# OOBD-Tiger.net
KiCad netlist of a schematic drawn in EAGLE
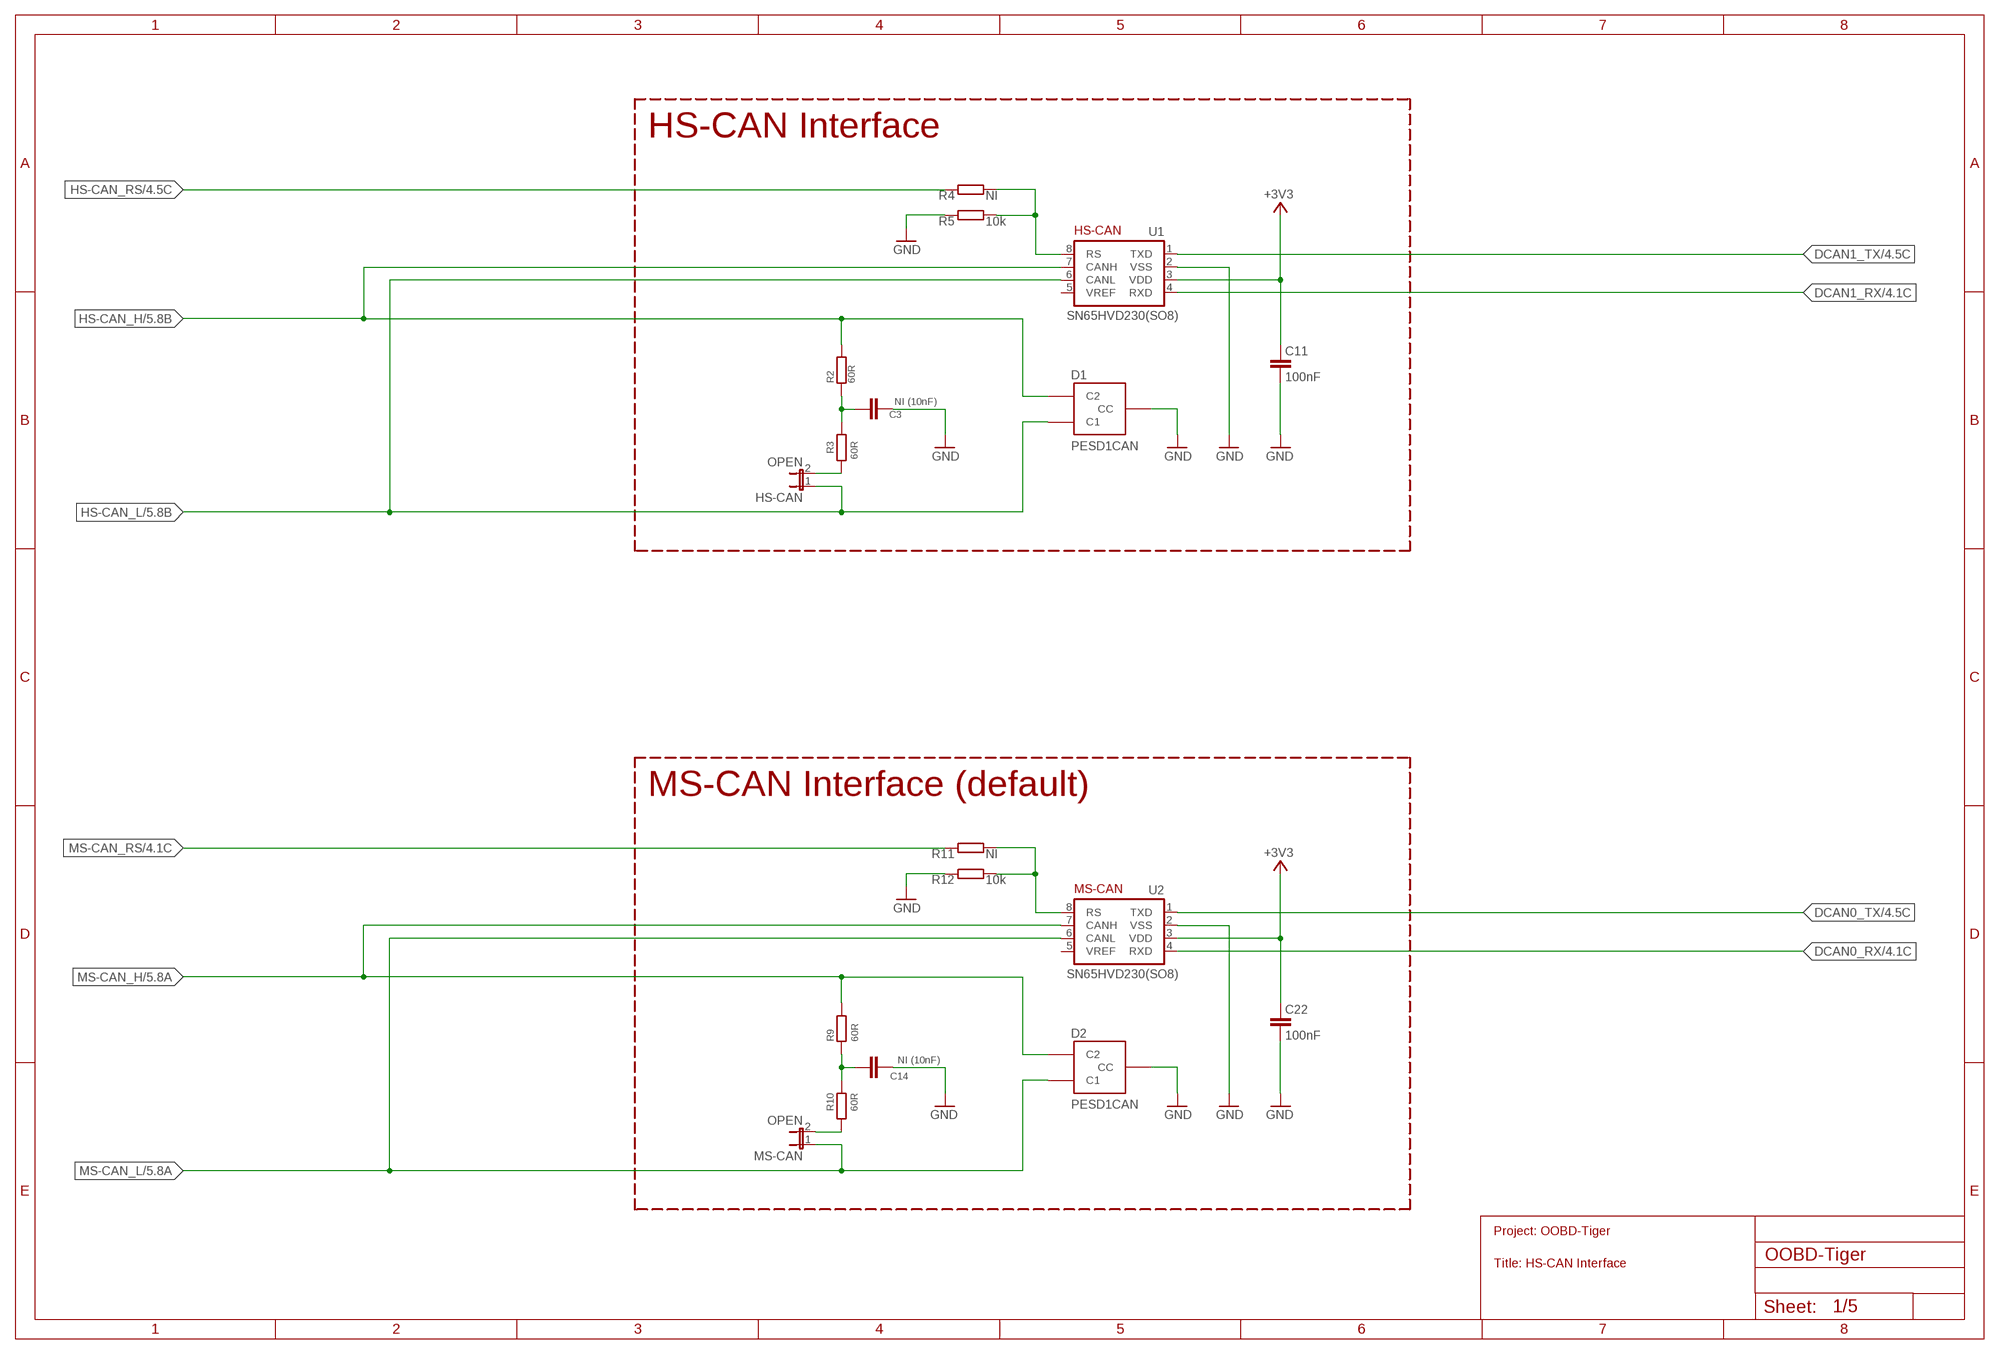
[diagram p0: schematic, sheet 1]
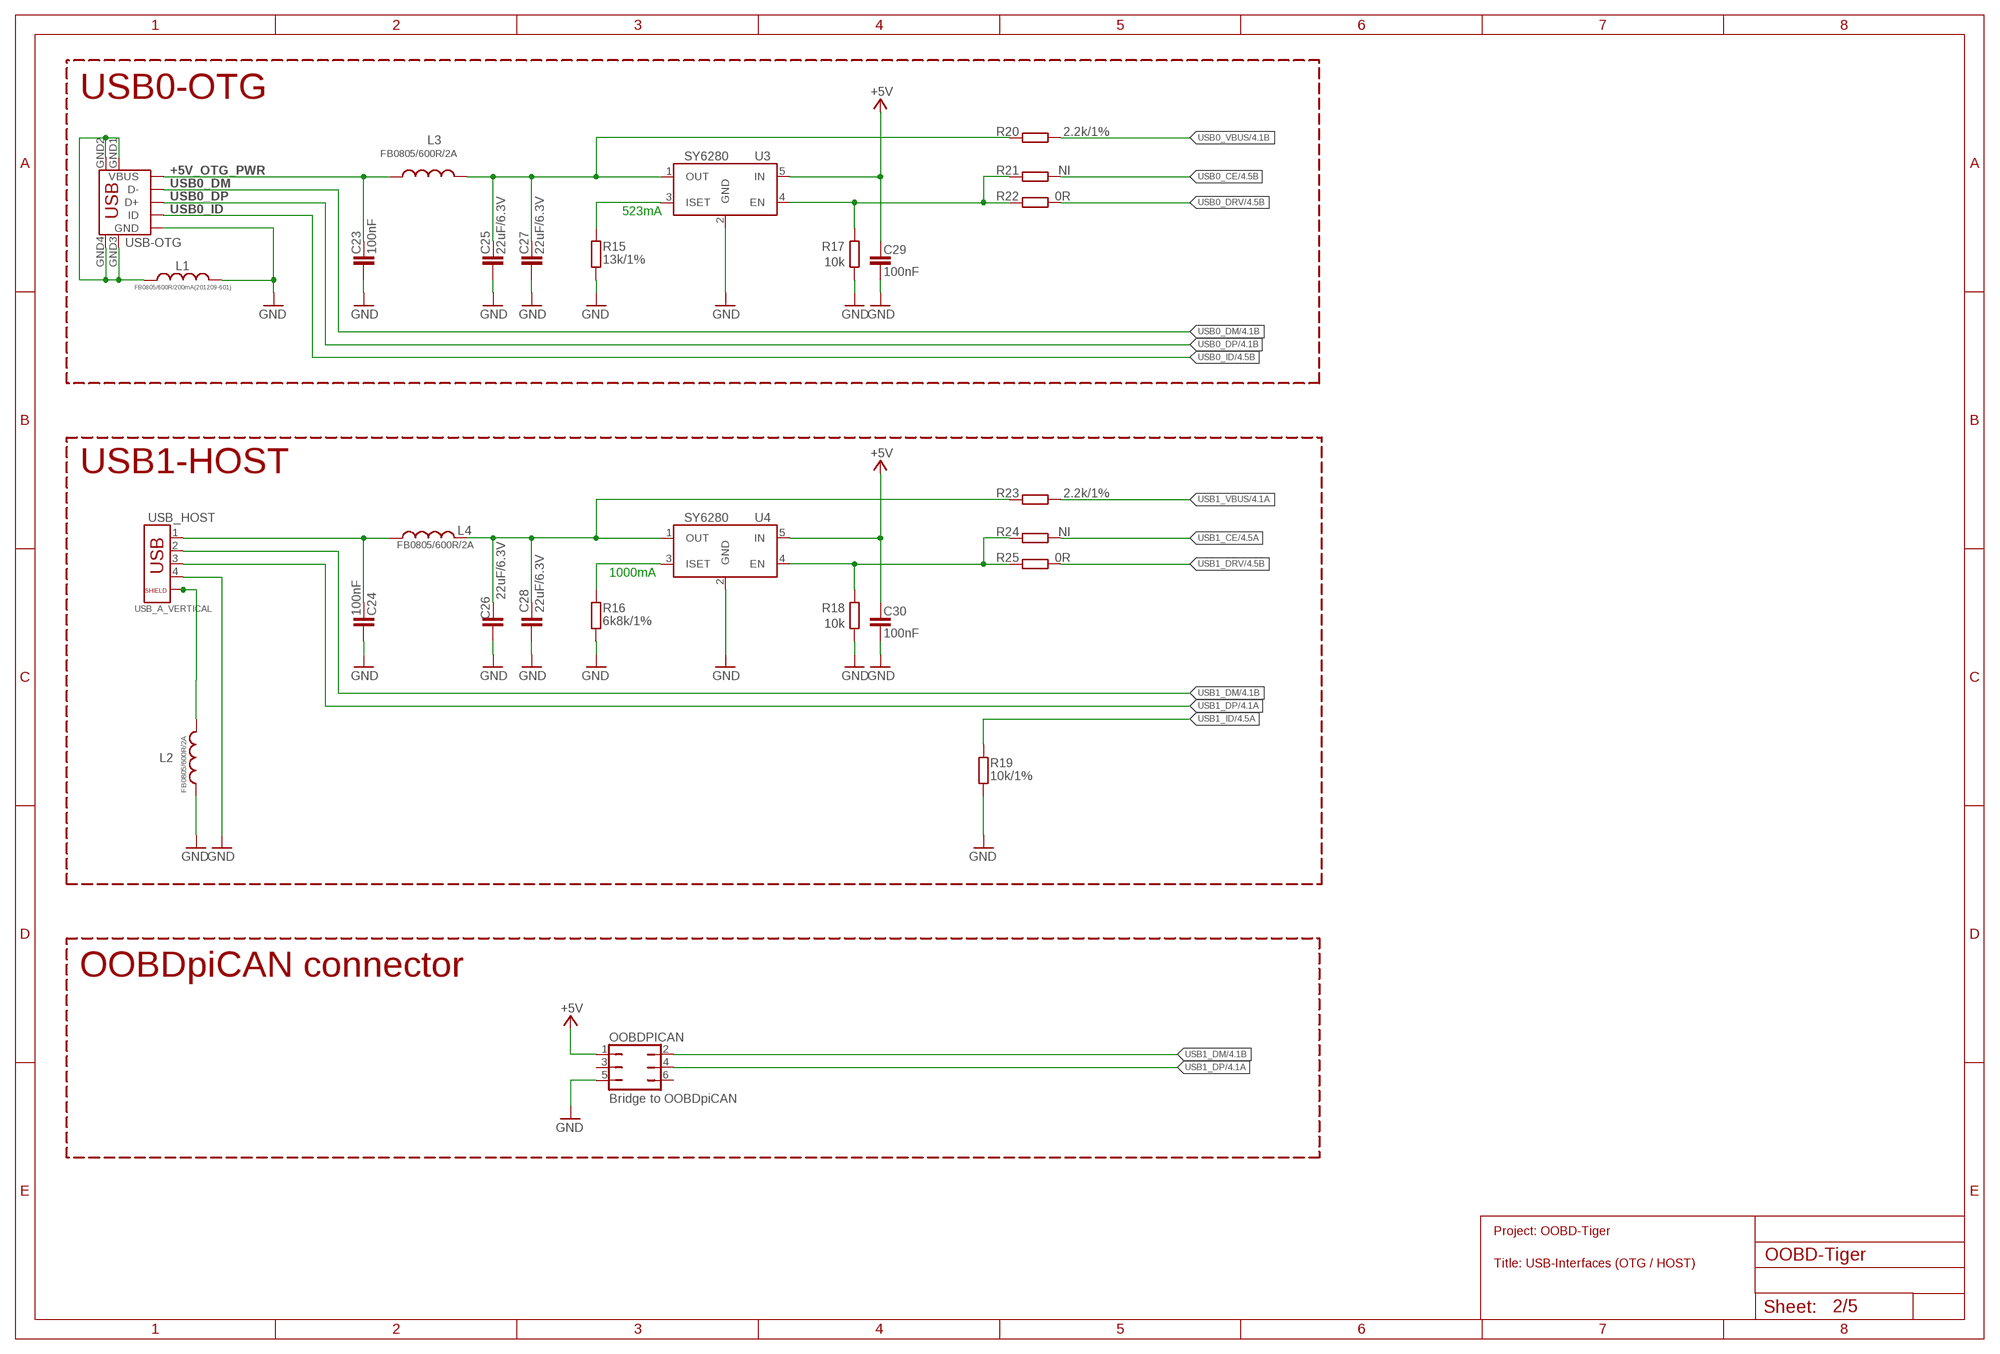
[diagram p1: schematic, sheet 2]
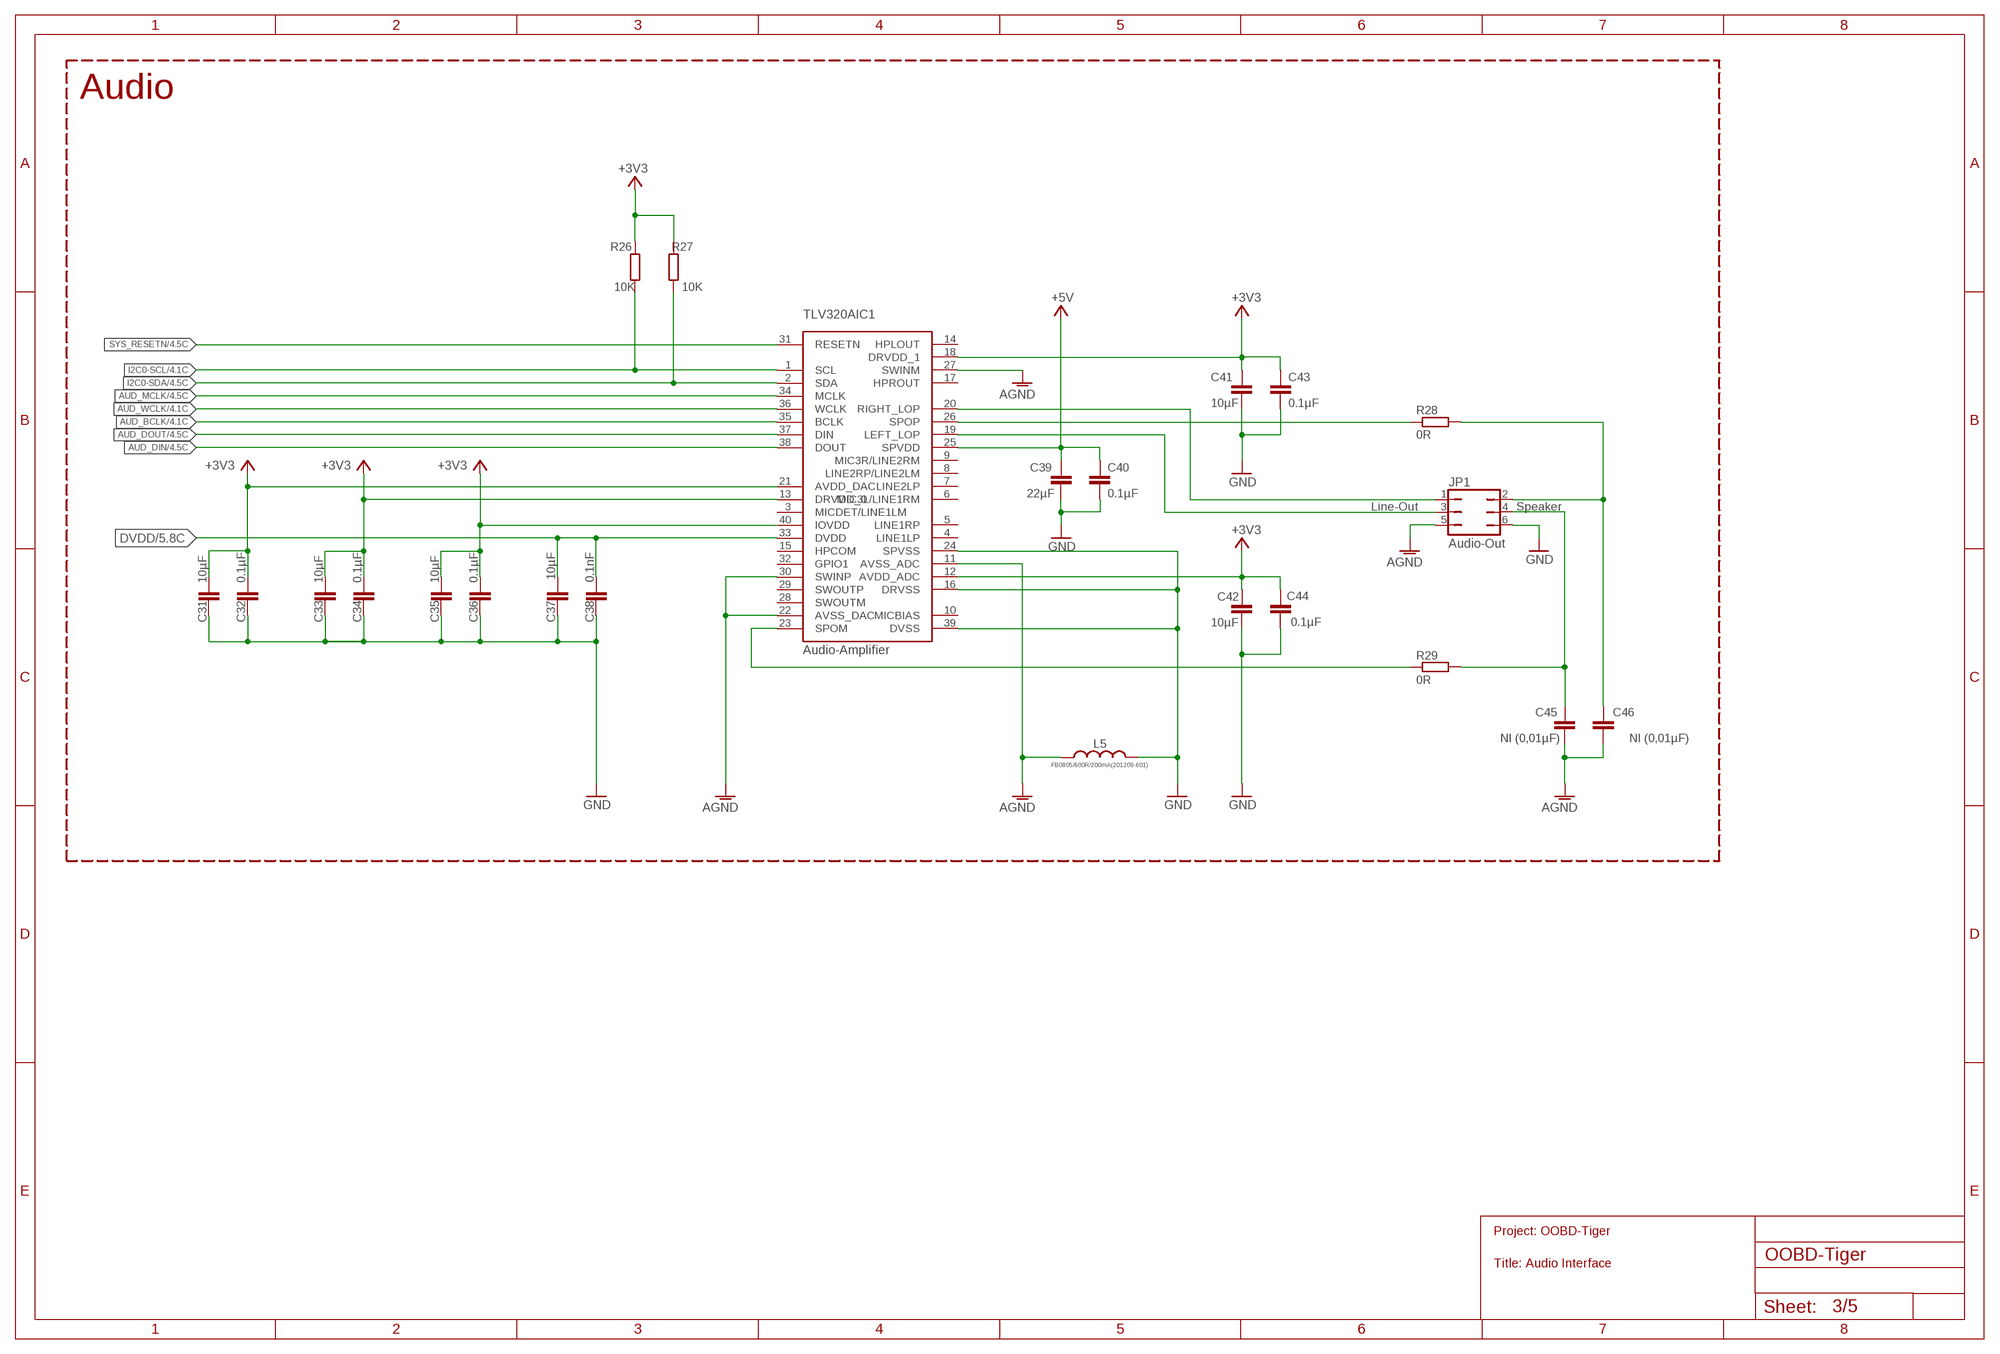
[diagram p2: schematic, sheet 3]
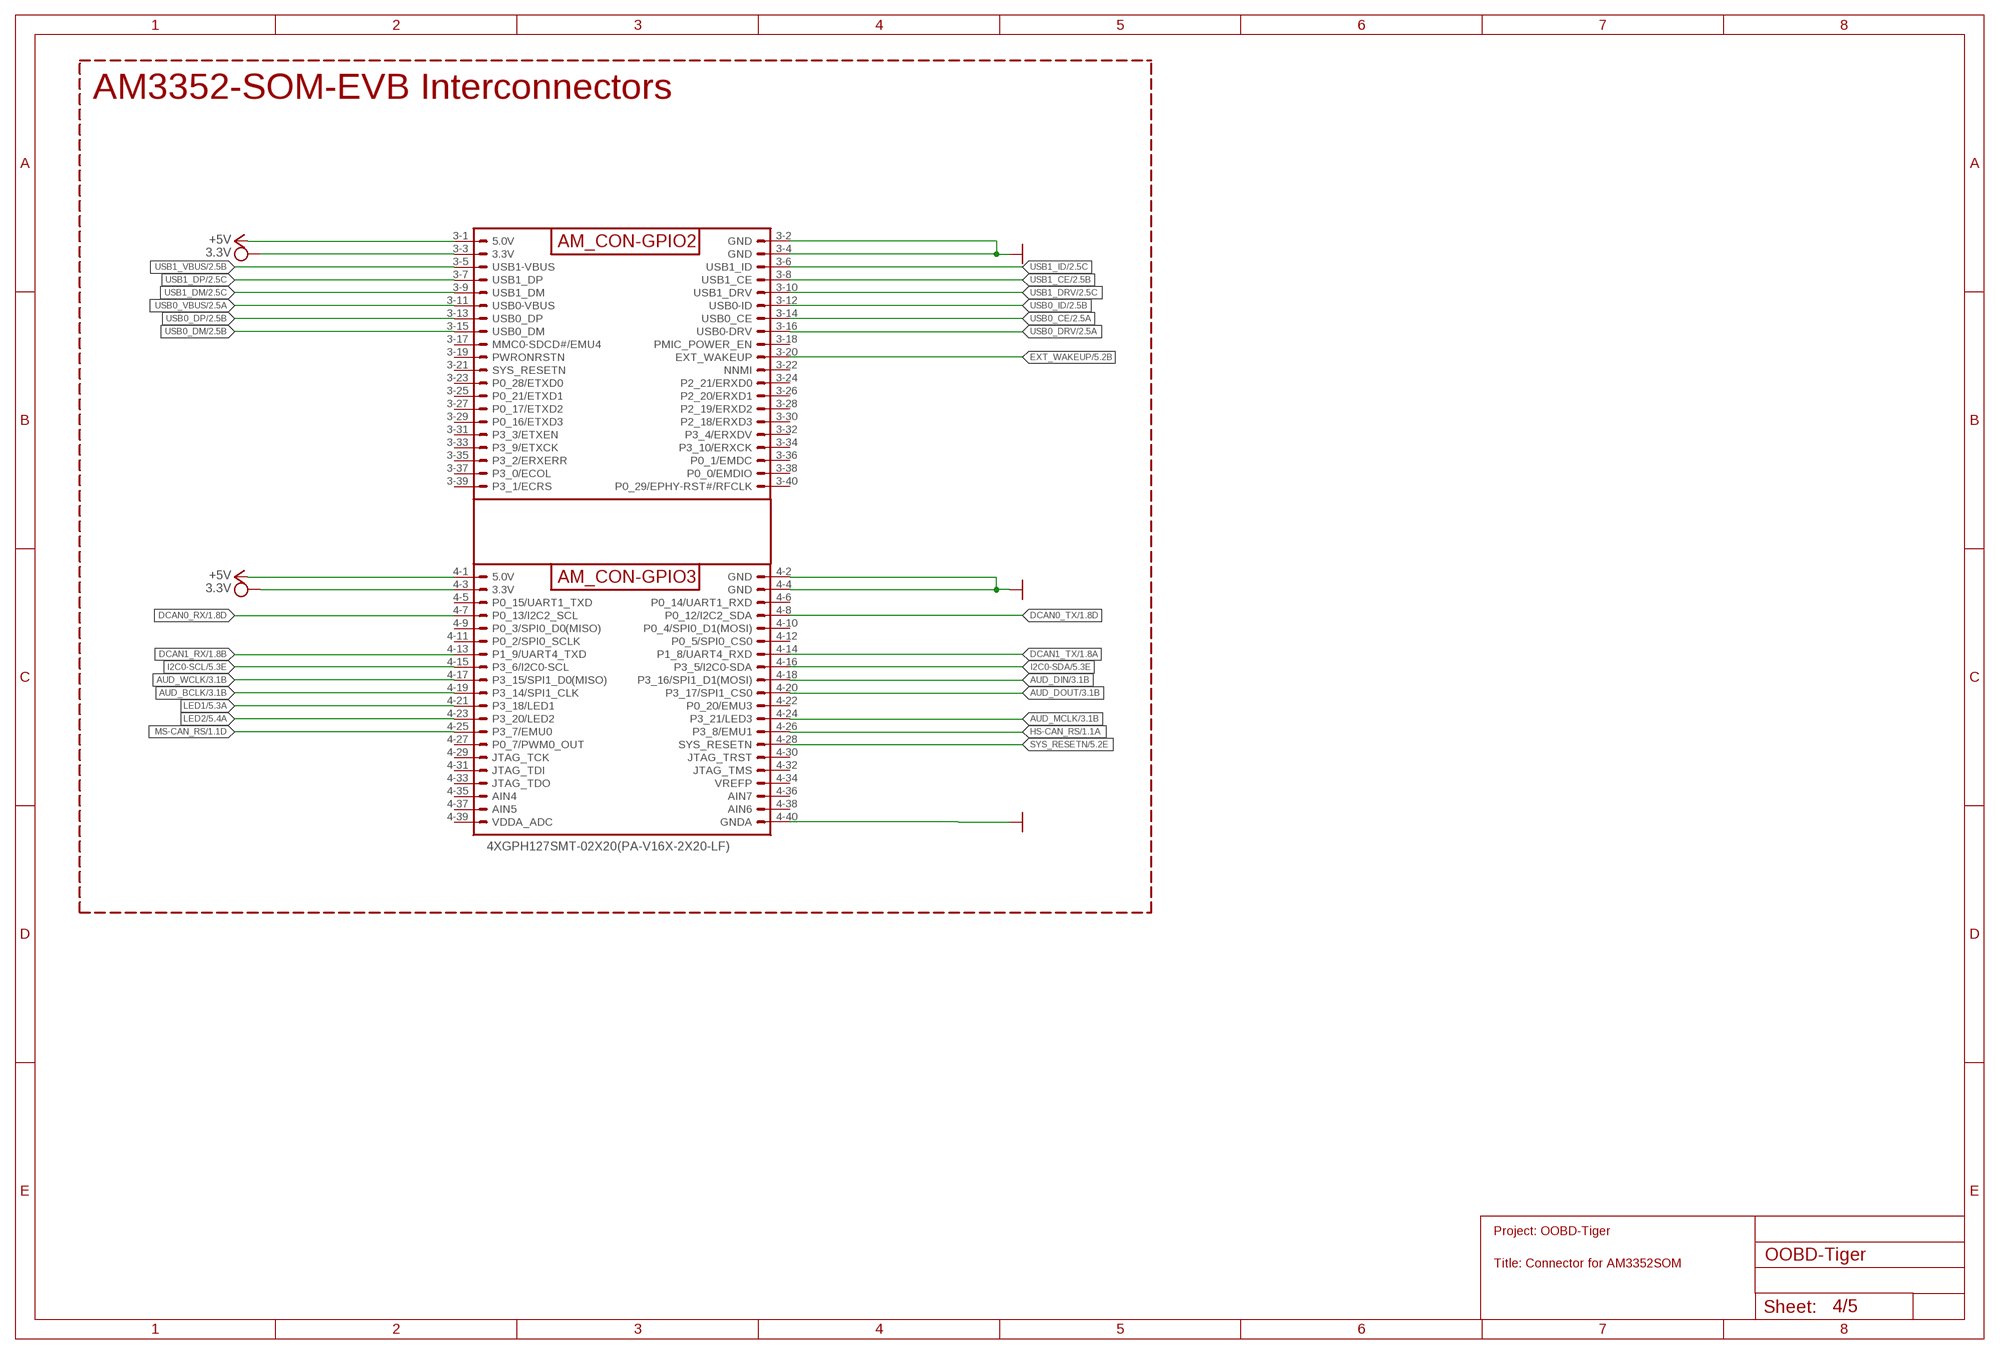
[diagram p3: schematic, sheet 4]
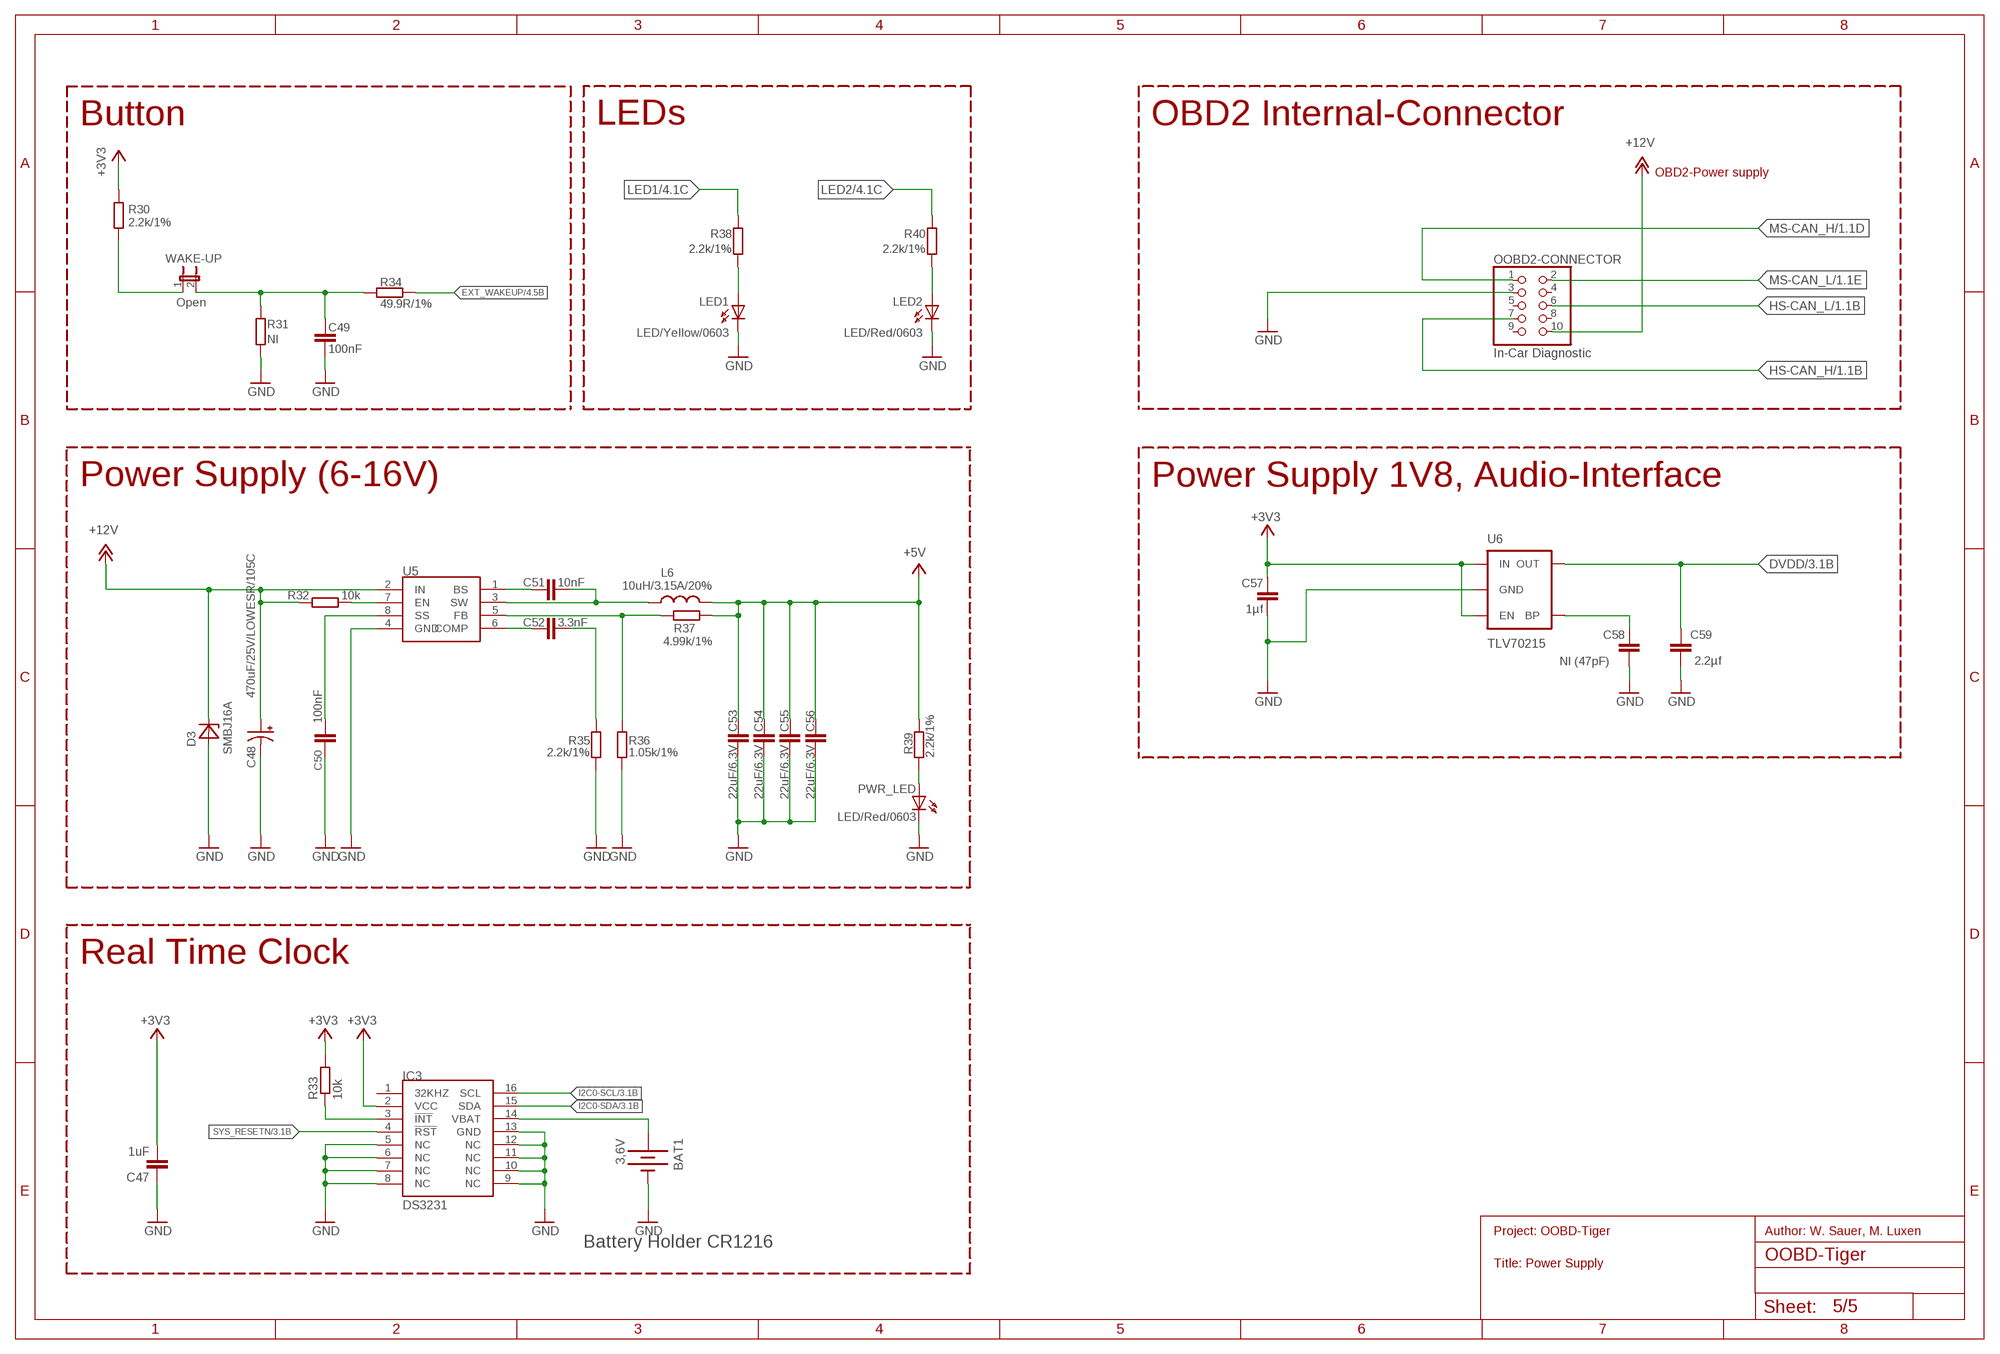
[diagram p4: schematic, sheet 5]

(export (version "E")
  (design (tool "Eeschema 10.0.6"))
  (components
    (comp (ref "C31")
      (value "10µF")
      (footprint "eagle-import:0603-CAP")
      (libsource (lib "eagle-import") (part "CAP0603-CAP"))
    )
    (comp (ref "C32")
      (value "0.1µF")
      (footprint "eagle-import:0603-CAP")
      (libsource (lib "eagle-import") (part "CAP0603-CAP"))
    )
    (comp (ref "C33")
      (value "10µF")
      (footprint "eagle-import:0603-CAP")
      (libsource (lib "eagle-import") (part "CAP0603-CAP"))
    )
    (comp (ref "C34")
      (value "0.1µF")
      (footprint "eagle-import:0603-CAP")
      (libsource (lib "eagle-import") (part "CAP0603-CAP"))
    )
    (comp (ref "C35")
      (value "10µF")
      (footprint "eagle-import:0603-CAP")
      (libsource (lib "eagle-import") (part "CAP0603-CAP"))
    )
    (comp (ref "C36")
      (value "0.1µF")
      (footprint "eagle-import:0603-CAP")
      (libsource (lib "eagle-import") (part "CAP0603-CAP"))
    )
    (comp (ref "C37")
      (value "10µF")
      (footprint "eagle-import:0603-CAP")
      (libsource (lib "eagle-import") (part "CAP0603-CAP"))
    )
    (comp (ref "C38")
      (value "0.1nF")
      (footprint "eagle-import:0603-CAP")
      (libsource (lib "eagle-import") (part "CAP0603-CAP"))
    )
    (comp (ref "C39")
      (value "22µF")
      (footprint "eagle-import:0603-CAP")
      (libsource (lib "eagle-import") (part "CAP0603-CAP"))
    )
    (comp (ref "C40")
      (value "0.1µF")
      (footprint "eagle-import:0603-CAP")
      (libsource (lib "eagle-import") (part "CAP0603-CAP"))
    )
    (comp (ref "C41")
      (value "10µF")
      (footprint "eagle-import:0603-CAP")
      (libsource (lib "eagle-import") (part "CAP0603-CAP"))
    )
    (comp (ref "C42")
      (value "10µF")
      (footprint "eagle-import:0603-CAP")
      (libsource (lib "eagle-import") (part "CAP0603-CAP"))
    )
    (comp (ref "C43")
      (value "0.1µF")
      (footprint "eagle-import:0603-CAP")
      (libsource (lib "eagle-import") (part "CAP0603-CAP"))
    )
    (comp (ref "C44")
      (value "0.1µF")
      (footprint "eagle-import:0603-CAP")
      (libsource (lib "eagle-import") (part "CAP0603-CAP"))
    )
    (comp (ref "C45")
      (value "NI (0,01µF)")
      (footprint "eagle-import:0603-CAP")
      (libsource (lib "eagle-import") (part "CAP0603-CAP"))
    )
    (comp (ref "C46")
      (value "NI (0,01µF)")
      (footprint "eagle-import:0603-CAP")
      (libsource (lib "eagle-import") (part "CAP0603-CAP"))
    )
    (comp (ref "JP1")
      (value "Audio-Out")
      (footprint "eagle-import:JP3Q")
      (libsource (lib "eagle-import") (part "JP3Q"))
    )
    (comp (ref "L5")
      (value "FB0805/600R/200mA(201209-601)")
      (footprint "eagle-import:L0603")
      (libsource (lib "eagle-import") (part "L-USL0603"))
    )
    (comp (ref "R26")
      (value "10K")
      (footprint "eagle-import:R0603")
      (libsource (lib "eagle-import") (part "resistor_R-EU_R0603"))
    )
    (comp (ref "R27")
      (value "10K")
      (footprint "eagle-import:R0603")
      (libsource (lib "eagle-import") (part "resistor_R-EU_R0603"))
    )
    (comp (ref "R28")
      (value "0R")
      (footprint "eagle-import:R0805")
      (libsource (lib "eagle-import") (part "resistor_R-EU_R0805"))
    )
    (comp (ref "R29")
      (value "0R")
      (footprint "eagle-import:R0805")
      (libsource (lib "eagle-import") (part "resistor_R-EU_R0805"))
    )
    (comp (ref "TLV320AIC1")
      (value "Audio-Amplifier")
      (footprint "eagle-import:QFN40-6X6")
      (libsource (lib "eagle-import") (part "TLV320AIC3107"))
    )
    (comp (ref "C3")
      (value "NI (10nF)")
      (footprint "eagle-import:C0603")
      (libsource (lib "eagle-import") (part "resistor_C-EUC0603"))
    )
    (comp (ref "C11")
      (value "100nF")
      (footprint "eagle-import:C0603K")
      (libsource (lib "eagle-import") (part "C-EUC0603K"))
    )
    (comp (ref "C14")
      (value "NI (10nF)")
      (footprint "eagle-import:C0603")
      (libsource (lib "eagle-import") (part "resistor_C-EUC0603"))
    )
    (comp (ref "C22")
      (value "100nF")
      (footprint "eagle-import:C0603K")
      (libsource (lib "eagle-import") (part "C-EUC0603K"))
    )
    (comp (ref "D1")
      (value "PESD1CAN")
      (footprint "eagle-import:SOT23")
      (libsource (lib "eagle-import") (part "PESD1CAN"))
    )
    (comp (ref "D2")
      (value "PESD1CAN")
      (footprint "eagle-import:SOT23")
      (libsource (lib "eagle-import") (part "PESD1CAN"))
    )
    (comp (ref "HS-CAN")
      (value "OPEN")
      (footprint "eagle-import:1X02")
      (libsource (lib "eagle-import") (part "JUMPER-2PTH"))
    )
    (comp (ref "MS-CAN")
      (value "OPEN")
      (footprint "eagle-import:1X02")
      (libsource (lib "eagle-import") (part "JUMPER-2PTH"))
    )
    (comp (ref "R2")
      (value "60R")
      (footprint "eagle-import:R0603")
      (libsource (lib "eagle-import") (part "resistor_R-EU_R0603"))
    )
    (comp (ref "R3")
      (value "60R")
      (footprint "eagle-import:R0603")
      (libsource (lib "eagle-import") (part "resistor_R-EU_R0603"))
    )
    (comp (ref "R4")
      (value "NI")
      (footprint "eagle-import:R0603")
      (libsource (lib "eagle-import") (part "R-EU_R0603"))
    )
    (comp (ref "R5")
      (value "10k")
      (footprint "eagle-import:R0603")
      (libsource (lib "eagle-import") (part "R-EU_R0603"))
    )
    (comp (ref "R9")
      (value "60R")
      (footprint "eagle-import:R0603")
      (libsource (lib "eagle-import") (part "resistor_R-EU_R0603"))
    )
    (comp (ref "R10")
      (value "60R")
      (footprint "eagle-import:R0603")
      (libsource (lib "eagle-import") (part "resistor_R-EU_R0603"))
    )
    (comp (ref "R11")
      (value "NI")
      (footprint "eagle-import:R0603")
      (libsource (lib "eagle-import") (part "R-EU_R0603"))
    )
    (comp (ref "R12")
      (value "10k")
      (footprint "eagle-import:R0603")
      (libsource (lib "eagle-import") (part "R-EU_R0603"))
    )
    (comp (ref "U1")
      (value "SN65HVD230(SO8)")
      (footprint "eagle-import:SO-08")
      (libsource (lib "eagle-import") (part "MCP2551"))
    )
    (comp (ref "U2")
      (value "SN65HVD230(SO8)")
      (footprint "eagle-import:SO-08")
      (libsource (lib "eagle-import") (part "MCP2551"))
    )
    (comp (ref "BAT1")
      (value "3,6V")
      (footprint "eagle-import:BATTCON_12MM_PTH")
      (libsource (lib "eagle-import") (part "BATTERY12PTH"))
    )
    (comp (ref "C47")
      (value "1uF")
      (footprint "eagle-import:C0603")
      (libsource (lib "eagle-import") (part "C-EUC0603"))
    )
    (comp (ref "C48")
      (value "470uF/25V/LOWESR/105C")
      (footprint "eagle-import:PANASONIC_D")
      (libsource (lib "eagle-import") (part "47UF-50V-20%(ELECT)"))
    )
    (comp (ref "C49")
      (value "100nF")
      (footprint "eagle-import:C0603")
      (libsource (lib "eagle-import") (part "C-EUC0603"))
    )
    (comp (ref "C50")
      (value "100nF")
      (footprint "eagle-import:C0603")
      (libsource (lib "eagle-import") (part "C-EUC0603"))
    )
    (comp (ref "C51")
      (value "10nF")
      (footprint "eagle-import:C0603")
      (libsource (lib "eagle-import") (part "C-EUC0603"))
    )
    (comp (ref "C52")
      (value "3.3nF")
      (footprint "eagle-import:C0603")
      (libsource (lib "eagle-import") (part "C-EUC0603"))
    )
    (comp (ref "C53")
      (value "22uF/6.3V")
      (footprint "eagle-import:C0603")
      (libsource (lib "eagle-import") (part "C-EUC0603"))
    )
    (comp (ref "C54")
      (value "22uF/6.3V")
      (footprint "eagle-import:C0603")
      (libsource (lib "eagle-import") (part "C-EUC0603"))
    )
    (comp (ref "C55")
      (value "22uF/6.3V")
      (footprint "eagle-import:C0603")
      (libsource (lib "eagle-import") (part "C-EUC0603"))
    )
    (comp (ref "C56")
      (value "22uF/6.3V")
      (footprint "eagle-import:C0603")
      (libsource (lib "eagle-import") (part "C-EUC0603"))
    )
    (comp (ref "C57")
      (value "1µf")
      (footprint "eagle-import:0603-CAP")
      (libsource (lib "eagle-import") (part "CAP0603-CAP"))
    )
    (comp (ref "C58")
      (value "NI (47pF)")
      (footprint "eagle-import:0603-CAP")
      (libsource (lib "eagle-import") (part "CAP0603-CAP"))
    )
    (comp (ref "C59")
      (value "2.2µf")
      (footprint "eagle-import:0603-CAP")
      (libsource (lib "eagle-import") (part "CAP0603-CAP"))
    )
    (comp (ref "D3")
      (value "SMBJ16A")
      (footprint "eagle-import:DO214AA")
      (libsource (lib "eagle-import") (part "SMBJ16A"))
    )
    (comp (ref "IC3")
      (value "DS3231")
      (footprint "eagle-import:SOIC-16W")
      (libsource (lib "eagle-import") (part "DS3231SOIC-16W"))
    )
    (comp (ref "L6")
      (value "10uH/3.15A/20%")
      (footprint "eagle-import:8X8MM_3131")
      (libsource (lib "eagle-import") (part "LLQH88PN100M38"))
    )
    (comp (ref "LED1")
      (value "LED/Yellow/0603")
      (footprint "eagle-import:LED_0603")
      (libsource (lib "eagle-import") (part "LEDLED_0603"))
    )
    (comp (ref "LED2")
      (value "LED/Red/0603")
      (footprint "eagle-import:LED_0603")
      (libsource (lib "eagle-import") (part "LEDLED_0603"))
    )
    (comp (ref "OOBD2-CONNECTOR")
      (value "In-Car Diagnostic")
      (footprint "eagle-import:2X05_90")
      (libsource (lib "eagle-import") (part "PINHD-2X5/90"))
    )
    (comp (ref "PWR_LED")
      (value "LED/Red/0603")
      (footprint "eagle-import:LED-0603")
      (libsource (lib "eagle-import") (part "LED0603DWS"))
    )
    (comp (ref "R30")
      (value "2.2k/1%")
      (footprint "eagle-import:R0603")
      (libsource (lib "eagle-import") (part "R-EU_R0603"))
    )
    (comp (ref "R31")
      (value "NI")
      (footprint "eagle-import:R0603")
      (libsource (lib "eagle-import") (part "R-EU_R0603"))
    )
    (comp (ref "R32")
      (value "10k")
      (footprint "eagle-import:R0603")
      (libsource (lib "eagle-import") (part "R-EU_R0603"))
    )
    (comp (ref "R33")
      (value "10k")
      (footprint "eagle-import:R0603")
      (libsource (lib "eagle-import") (part "R-EU_R0603"))
    )
    (comp (ref "R34")
      (value "49.9R/1%")
      (footprint "eagle-import:R0603")
      (libsource (lib "eagle-import") (part "R-EU_R0603"))
    )
    (comp (ref "R35")
      (value "2.2k/1%")
      (footprint "eagle-import:R0603")
      (libsource (lib "eagle-import") (part "R-EU_R0603"))
    )
    (comp (ref "R36")
      (value "1.05k/1%")
      (footprint "eagle-import:R0603")
      (libsource (lib "eagle-import") (part "R-EU_R0603"))
    )
    (comp (ref "R37")
      (value "4.99k/1%")
      (footprint "eagle-import:R0603")
      (libsource (lib "eagle-import") (part "R-EU_R0603"))
    )
    (comp (ref "R38")
      (value "2.2k/1%")
      (footprint "eagle-import:R0603")
      (libsource (lib "eagle-import") (part "R-EU_R0603"))
    )
    (comp (ref "R39")
      (value "2.2k/1%")
      (footprint "eagle-import:R0603")
      (libsource (lib "eagle-import") (part "R-EU_R0603"))
    )
    (comp (ref "R40")
      (value "2.2k/1%")
      (footprint "eagle-import:R0603")
      (libsource (lib "eagle-import") (part "R-EU_R0603"))
    )
    (comp (ref "U5")
      (value "MP1482")
      (footprint "eagle-import:SOIC8")
      (libsource (lib "eagle-import") (part "MP1482"))
    )
    (comp (ref "U6")
      (value "TLV70215")
      (footprint "eagle-import:SOT23-5")
      (libsource (lib "eagle-import") (part "V_REG_LDOSMD"))
    )
    (comp (ref "WAKE-UP")
      (value "Open")
      (footprint "eagle-import:1X02_LOCK")
      (libsource (lib "eagle-import") (part "JUMPER-2PTH_LOCK"))
    )
    (comp (ref "C23")
      (value "100nF")
      (footprint "eagle-import:C0603K")
      (libsource (lib "eagle-import") (part "C-EUC0603K"))
    )
    (comp (ref "C24")
      (value "100nF")
      (footprint "eagle-import:C0603K")
      (libsource (lib "eagle-import") (part "C-EUC0603K"))
    )
    (comp (ref "C25")
      (value "22uF/6.3V")
      (footprint "eagle-import:C0603")
      (libsource (lib "eagle-import") (part "C-EUC0603"))
    )
    (comp (ref "C26")
      (value "22uF/6.3V")
      (footprint "eagle-import:C0603")
      (libsource (lib "eagle-import") (part "C-EUC0603"))
    )
    (comp (ref "C27")
      (value "22uF/6.3V")
      (footprint "eagle-import:C0603")
      (libsource (lib "eagle-import") (part "C-EUC0603"))
    )
    (comp (ref "C28")
      (value "22uF/6.3V")
      (footprint "eagle-import:C0603")
      (libsource (lib "eagle-import") (part "C-EUC0603"))
    )
    (comp (ref "C29")
      (value "100nF")
      (footprint "eagle-import:C0603K")
      (libsource (lib "eagle-import") (part "C-EUC0603K"))
    )
    (comp (ref "C30")
      (value "100nF")
      (footprint "eagle-import:C0603K")
      (libsource (lib "eagle-import") (part "C-EUC0603K"))
    )
    (comp (ref "L1")
      (value "FB0805/600R/200mA(201209-601)")
      (footprint "eagle-import:L0603")
      (libsource (lib "eagle-import") (part "L-USL0603"))
    )
    (comp (ref "L2")
      (value "FB0805/600R/2A")
      (footprint "eagle-import:L0603")
      (libsource (lib "eagle-import") (part "L-USL0603"))
    )
    (comp (ref "L3")
      (value "FB0805/600R/2A")
      (footprint "eagle-import:L0603")
      (libsource (lib "eagle-import") (part "L-USL0603"))
    )
    (comp (ref "L4")
      (value "FB0805/600R/2A")
      (footprint "eagle-import:L0603")
      (libsource (lib "eagle-import") (part "L-USL0603"))
    )
    (comp (ref "OOBDPICAN")
      (value "Bridge to OOBDpiCAN")
      (footprint "eagle-import:JP3Q")
      (libsource (lib "eagle-import") (part "JP3Q"))
    )
    (comp (ref "R15")
      (value "13k/1%")
      (footprint "eagle-import:R0603")
      (libsource (lib "eagle-import") (part "R-EU_R0603"))
    )
    (comp (ref "R16")
      (value "6k8k/1%")
      (footprint "eagle-import:R0603")
      (libsource (lib "eagle-import") (part "R-EU_R0603"))
    )
    (comp (ref "R17")
      (value "10k")
      (footprint "eagle-import:R0603")
      (libsource (lib "eagle-import") (part "R-EU_R0603"))
    )
    (comp (ref "R18")
      (value "10k")
      (footprint "eagle-import:R0603")
      (libsource (lib "eagle-import") (part "R-EU_R0603"))
    )
    (comp (ref "R19")
      (value "10k/1%")
      (footprint "eagle-import:R0603")
      (libsource (lib "eagle-import") (part "R-EU_R0603"))
    )
    (comp (ref "R20")
      (value "2.2k/1%")
      (footprint "eagle-import:R0603")
      (libsource (lib "eagle-import") (part "R-EU_R0603"))
    )
    (comp (ref "R21")
      (value "NI")
      (footprint "eagle-import:R0603")
      (libsource (lib "eagle-import") (part "R-EU_R0603"))
    )
    (comp (ref "R22")
      (value "0R")
      (footprint "eagle-import:R0603")
      (libsource (lib "eagle-import") (part "R-EU_R0603"))
    )
    (comp (ref "R23")
      (value "2.2k/1%")
      (footprint "eagle-import:R0603")
      (libsource (lib "eagle-import") (part "R-EU_R0603"))
    )
    (comp (ref "R24")
      (value "NI")
      (footprint "eagle-import:R0603")
      (libsource (lib "eagle-import") (part "R-EU_R0603"))
    )
    (comp (ref "R25")
      (value "0R")
      (footprint "eagle-import:R0603")
      (libsource (lib "eagle-import") (part "R-EU_R0603"))
    )
    (comp (ref "U3")
      (value "SY6280")
      (footprint "eagle-import:SOT23-5")
      (libsource (lib "eagle-import") (part "SY6280"))
    )
    (comp (ref "U4")
      (value "SY6280")
      (footprint "eagle-import:SOT23-5")
      (libsource (lib "eagle-import") (part "SY6280"))
    )
    (comp (ref "USB_HOST")
      (value "USB_A_VERTICAL")
      (footprint "eagle-import:USB_PN87520_DEV_PTH")
      (libsource (lib "eagle-import") (part "USB_SHIELD1"))
    )
    (comp (ref "USB_OTG")
      (value "USB-OTG")
      (footprint "eagle-import:USB_MINI_9PIN")
      (libsource (lib "eagle-import") (part "MINI_USB9"))
    )
    (comp (ref "AM3352-SOM-EVB-PLATFORM")
      (value "4XGPH127SMT-02X20(PA-V16X-2X20-LF)")
      (footprint "eagle-import:OOBD-TIGER-AM3352-SOM")
      (libsource (lib "eagle-import") (part "OOBD-TIGER-AM3352-SOM---4XGPH127SMT-02X20(PA-V16X-2X20-LF)"))
    )
  )
  (nets
    (net (code "1") (name "+3V3") (class "Default")
      (node (ref "C11") (pin "1") (pinfunction "1_1") (pintype "passive"))
      (node (ref "C22") (pin "1") (pinfunction "1_1") (pintype "passive"))
      (node (ref "C31") (pin "2") (pinfunction "2_2") (pintype "passive"))
      (node (ref "C32") (pin "2") (pinfunction "2_2") (pintype "passive"))
      (node (ref "C33") (pin "2") (pinfunction "2_2") (pintype "passive"))
      (node (ref "C34") (pin "2") (pinfunction "2_2") (pintype "passive"))
      (node (ref "C35") (pin "2") (pinfunction "2_2") (pintype "passive"))
      (node (ref "C36") (pin "2") (pinfunction "2_2") (pintype "passive"))
      (node (ref "C41") (pin "1") (pinfunction "1_1") (pintype "passive"))
      (node (ref "C42") (pin "1") (pinfunction "1_1") (pintype "passive"))
      (node (ref "C43") (pin "1") (pinfunction "1_1") (pintype "passive"))
      (node (ref "C44") (pin "1") (pinfunction "1_1") (pintype "passive"))
      (node (ref "C47") (pin "2") (pinfunction "2_2") (pintype "passive"))
      (node (ref "C57") (pin "2") (pinfunction "2_2") (pintype "passive"))
      (node (ref "IC3") (pin "2") (pinfunction "VCC_2") (pintype "bidirectional"))
      (node (ref "R26") (pin "2") (pinfunction "2_2") (pintype "passive"))
      (node (ref "R27") (pin "2") (pinfunction "2_2") (pintype "passive"))
      (node (ref "R30") (pin "2") (pinfunction "2_2") (pintype "passive"))
      (node (ref "R33") (pin "2") (pinfunction "2_2") (pintype "passive"))
      (node (ref "TLV320AIC1") (pin "12") (pinfunction "AVDD_ADC_12") (pintype "bidirectional"))
      (node (ref "TLV320AIC1") (pin "13") (pinfunction "DRVDD_0_13") (pintype "bidirectional"))
      (node (ref "TLV320AIC1") (pin "18") (pinfunction "DRVDD_1_18") (pintype "bidirectional"))
      (node (ref "TLV320AIC1") (pin "21") (pinfunction "AVDD_DAC_21") (pintype "bidirectional"))
      (node (ref "TLV320AIC1") (pin "40") (pinfunction "IOVDD_40") (pintype "bidirectional"))
      (node (ref "U1") (pin "3") (pinfunction "VDD_3") (pintype "power_in"))
      (node (ref "U2") (pin "3") (pinfunction "VDD_3") (pintype "power_in"))
      (node (ref "U6") (pin "1") (pinfunction "IN_1") (pintype "input"))
      (node (ref "U6") (pin "3") (pinfunction "EN_3") (pintype "input"))
    )
    (net (code "2") (name "+5V") (class "Default")
      (node (ref "AM3352-SOM-EVB-PLATFORM") (pin "3-1") (pinfunction "5.0V_3-1") (pintype "passive"))
      (node (ref "AM3352-SOM-EVB-PLATFORM") (pin "4-1") (pinfunction "5.0V_4-1") (pintype "passive"))
      (node (ref "C29") (pin "1") (pinfunction "1_1") (pintype "passive"))
      (node (ref "C30") (pin "1") (pinfunction "1_1") (pintype "passive"))
      (node (ref "C39") (pin "2") (pinfunction "2_2") (pintype "passive"))
      (node (ref "C40") (pin "2") (pinfunction "2_2") (pintype "passive"))
      (node (ref "C53") (pin "1") (pinfunction "1_1") (pintype "passive"))
      (node (ref "C54") (pin "1") (pinfunction "1_1") (pintype "passive"))
      (node (ref "C55") (pin "1") (pinfunction "1_1") (pintype "passive"))
      (node (ref "C56") (pin "1") (pinfunction "1_1") (pintype "passive"))
      (node (ref "L6") (pin "2") (pinfunction "2_2") (pintype "passive"))
      (node (ref "OOBDPICAN") (pin "1") (pinfunction "1_1") (pintype "passive"))
      (node (ref "R37") (pin "2") (pinfunction "2_2") (pintype "passive"))
      (node (ref "R39") (pin "1") (pinfunction "1_1") (pintype "passive"))
      (node (ref "TLV320AIC1") (pin "25") (pinfunction "SPVDD_25") (pintype "bidirectional"))
      (node (ref "U3") (pin "5") (pinfunction "IN_5") (pintype "power_in"))
      (node (ref "U4") (pin "5") (pinfunction "IN_5") (pintype "power_in"))
    )
    (net (code "3") (name "+5V_OTG_PWR") (class "Default")
      (node (ref "C23") (pin "1") (pinfunction "1_1") (pintype "passive"))
      (node (ref "L3") (pin "1") (pinfunction "1_1") (pintype "passive"))
      (node (ref "USB_OTG") (pin "VBUS") (pinfunction "VBUS_VBUS") (pintype "power_in"))
    )
    (net (code "4") (name "+12V") (class "Default")
      (node (ref "C48") (pin "+") (pinfunction "+_+") (pintype "passive"))
      (node (ref "D3") (pin "C") (pinfunction "C_C") (pintype "passive"))
      (node (ref "OOBD2-CONNECTOR") (pin "10") (pinfunction "10_10") (pintype "passive"))
      (node (ref "R32") (pin "1") (pinfunction "1_1") (pintype "passive"))
      (node (ref "U5") (pin "2") (pinfunction "IN_2") (pintype "bidirectional"))
    )
    (net (code "5") (name "3V3") (class "Default")
      (node (ref "AM3352-SOM-EVB-PLATFORM") (pin "3-3") (pinfunction "3.3V_3-3") (pintype "passive"))
      (node (ref "AM3352-SOM-EVB-PLATFORM") (pin "4-3") (pinfunction "3.3V_4-3") (pintype "passive"))
    )
    (net (code "6") (name "AGND") (class "Default")
      (node (ref "C45") (pin "1") (pinfunction "1_1") (pintype "passive"))
      (node (ref "C46") (pin "1") (pinfunction "1_1") (pintype "passive"))
      (node (ref "JP1") (pin "5") (pinfunction "5_5") (pintype "passive"))
      (node (ref "L5") (pin "2") (pinfunction "2_2") (pintype "passive"))
      (node (ref "TLV320AIC1") (pin "11") (pinfunction "AVSS_ADC_11") (pintype "bidirectional"))
      (node (ref "TLV320AIC1") (pin "22") (pinfunction "AVSS_DAC_22") (pintype "bidirectional"))
      (node (ref "TLV320AIC1") (pin "27") (pinfunction "SWINM_27") (pintype "bidirectional"))
      (node (ref "TLV320AIC1") (pin "30") (pinfunction "SWINP_30") (pintype "bidirectional"))
    )
    (net (code "7") (name "AUD_BCLK") (class "Default")
      (node (ref "AM3352-SOM-EVB-PLATFORM") (pin "4-19") (pinfunction "P3_14/SPI1_CLK_4-19") (pintype "passive"))
      (node (ref "TLV320AIC1") (pin "35") (pinfunction "BCLK_35") (pintype "bidirectional"))
    )
    (net (code "8") (name "AUD_DIN") (class "Default")
      (node (ref "AM3352-SOM-EVB-PLATFORM") (pin "4-18") (pinfunction "P3_16/SPI1_D1(MOSI)_4-18") (pintype "passive"))
      (node (ref "TLV320AIC1") (pin "38") (pinfunction "DOUT_38") (pintype "bidirectional"))
    )
    (net (code "9") (name "AUD_DOUT") (class "Default")
      (node (ref "AM3352-SOM-EVB-PLATFORM") (pin "4-20") (pinfunction "P3_17/SPI1_CS0_4-20") (pintype "passive"))
      (node (ref "TLV320AIC1") (pin "37") (pinfunction "DIN_37") (pintype "bidirectional"))
    )
    (net (code "10") (name "AUD_MCLK") (class "Default")
      (node (ref "AM3352-SOM-EVB-PLATFORM") (pin "4-24") (pinfunction "P3_21/LED3_4-24") (pintype "passive"))
      (node (ref "TLV320AIC1") (pin "34") (pinfunction "MCLK_34") (pintype "bidirectional"))
    )
    (net (code "11") (name "AUD_WCLK") (class "Default")
      (node (ref "AM3352-SOM-EVB-PLATFORM") (pin "4-17") (pinfunction "P3_15/SPI1_D0(MISO)_4-17") (pintype "passive"))
      (node (ref "TLV320AIC1") (pin "36") (pinfunction "WCLK_36") (pintype "bidirectional"))
    )
    (net (code "12") (name "DCAN0_RX") (class "Default")
      (node (ref "AM3352-SOM-EVB-PLATFORM") (pin "4-7") (pinfunction "P0_13/I2C2_SCL_4-7") (pintype "passive"))
      (node (ref "U2") (pin "4") (pinfunction "RXD_4") (pintype "output"))
    )
    (net (code "13") (name "DCAN0_TX") (class "Default")
      (node (ref "AM3352-SOM-EVB-PLATFORM") (pin "4-8") (pinfunction "P0_12/I2C2_SDA_4-8") (pintype "passive"))
      (node (ref "U2") (pin "1") (pinfunction "TXD_1") (pintype "input"))
    )
    (net (code "14") (name "DCAN1_RX") (class "Default")
      (node (ref "AM3352-SOM-EVB-PLATFORM") (pin "4-13") (pinfunction "P1_9/UART4_TXD_4-13") (pintype "passive"))
      (node (ref "U1") (pin "4") (pinfunction "RXD_4") (pintype "output"))
    )
    (net (code "15") (name "DCAN1_TX") (class "Default")
      (node (ref "AM3352-SOM-EVB-PLATFORM") (pin "4-14") (pinfunction "P1_8/UART4_RXD_4-14") (pintype "passive"))
      (node (ref "U1") (pin "1") (pinfunction "TXD_1") (pintype "input"))
    )
    (net (code "16") (name "DVDD") (class "Default")
      (node (ref "C37") (pin "2") (pinfunction "2_2") (pintype "passive"))
      (node (ref "C38") (pin "2") (pinfunction "2_2") (pintype "passive"))
      (node (ref "C59") (pin "2") (pinfunction "2_2") (pintype "passive"))
      (node (ref "TLV320AIC1") (pin "33") (pinfunction "DVDD_33") (pintype "bidirectional"))
      (node (ref "U6") (pin "5") (pinfunction "OUT_5") (pintype "passive"))
    )
    (net (code "17") (name "EXT_WAKEUP") (class "Default")
      (node (ref "AM3352-SOM-EVB-PLATFORM") (pin "3-20") (pinfunction "EXT_WAKEUP_3-20") (pintype "passive"))
      (node (ref "R34") (pin "1") (pinfunction "1_1") (pintype "passive"))
    )
    (net (code "18") (name "GND") (class "Default")
      (node (ref "AM3352-SOM-EVB-PLATFORM") (pin "3-2") (pinfunction "GND_3-2") (pintype "passive"))
      (node (ref "AM3352-SOM-EVB-PLATFORM") (pin "3-4") (pinfunction "GND_3-4") (pintype "passive"))
      (node (ref "AM3352-SOM-EVB-PLATFORM") (pin "4-2") (pinfunction "GND_4-2") (pintype "passive"))
      (node (ref "AM3352-SOM-EVB-PLATFORM") (pin "4-4") (pinfunction "GND_4-4") (pintype "passive"))
      (node (ref "AM3352-SOM-EVB-PLATFORM") (pin "4-40") (pinfunction "GNDA_4-40") (pintype "passive"))
      (node (ref "BAT1") (pin "GND") (pinfunction "-_GND") (pintype "power_in"))
      (node (ref "C11") (pin "2") (pinfunction "2_2") (pintype "passive"))
      (node (ref "C14") (pin "2") (pinfunction "2_2") (pintype "passive"))
      (node (ref "C22") (pin "2") (pinfunction "2_2") (pintype "passive"))
      (node (ref "C23") (pin "2") (pinfunction "2_2") (pintype "passive"))
      (node (ref "C24") (pin "2") (pinfunction "2_2") (pintype "passive"))
      (node (ref "C25") (pin "2") (pinfunction "2_2") (pintype "passive"))
      (node (ref "C26") (pin "2") (pinfunction "2_2") (pintype "passive"))
      (node (ref "C27") (pin "2") (pinfunction "2_2") (pintype "passive"))
      (node (ref "C28") (pin "2") (pinfunction "2_2") (pintype "passive"))
      (node (ref "C29") (pin "2") (pinfunction "2_2") (pintype "passive"))
      (node (ref "C3") (pin "2") (pinfunction "2_2") (pintype "passive"))
      (node (ref "C30") (pin "2") (pinfunction "2_2") (pintype "passive"))
      (node (ref "C31") (pin "1") (pinfunction "1_1") (pintype "passive"))
      (node (ref "C32") (pin "1") (pinfunction "1_1") (pintype "passive"))
      (node (ref "C33") (pin "1") (pinfunction "1_1") (pintype "passive"))
      (node (ref "C34") (pin "1") (pinfunction "1_1") (pintype "passive"))
      (node (ref "C35") (pin "1") (pinfunction "1_1") (pintype "passive"))
      (node (ref "C36") (pin "1") (pinfunction "1_1") (pintype "passive"))
      (node (ref "C37") (pin "1") (pinfunction "1_1") (pintype "passive"))
      (node (ref "C38") (pin "1") (pinfunction "1_1") (pintype "passive"))
      (node (ref "C39") (pin "1") (pinfunction "1_1") (pintype "passive"))
      (node (ref "C40") (pin "1") (pinfunction "1_1") (pintype "passive"))
      (node (ref "C41") (pin "2") (pinfunction "2_2") (pintype "passive"))
      (node (ref "C42") (pin "2") (pinfunction "2_2") (pintype "passive"))
      (node (ref "C43") (pin "2") (pinfunction "2_2") (pintype "passive"))
      (node (ref "C44") (pin "2") (pinfunction "2_2") (pintype "passive"))
      (node (ref "C47") (pin "1") (pinfunction "1_1") (pintype "passive"))
      (node (ref "C48") (pin "-") (pinfunction "-_-") (pintype "passive"))
      (node (ref "C49") (pin "2") (pinfunction "2_2") (pintype "passive"))
      (node (ref "C50") (pin "2") (pinfunction "2_2") (pintype "passive"))
      (node (ref "C53") (pin "2") (pinfunction "2_2") (pintype "passive"))
      (node (ref "C54") (pin "2") (pinfunction "2_2") (pintype "passive"))
      (node (ref "C55") (pin "2") (pinfunction "2_2") (pintype "passive"))
      (node (ref "C56") (pin "2") (pinfunction "2_2") (pintype "passive"))
      (node (ref "C57") (pin "1") (pinfunction "1_1") (pintype "passive"))
      (node (ref "C58") (pin "1") (pinfunction "1_1") (pintype "passive"))
      (node (ref "C59") (pin "1") (pinfunction "1_1") (pintype "passive"))
      (node (ref "D1") (pin "3") (pinfunction "CC_3") (pintype "bidirectional"))
      (node (ref "D2") (pin "3") (pinfunction "CC_3") (pintype "bidirectional"))
      (node (ref "D3") (pin "A") (pinfunction "A_A") (pintype "passive"))
      (node (ref "IC3") (pin "10") (pinfunction "NC_10") (pintype "bidirectional"))
      (node (ref "IC3") (pin "11") (pinfunction "NC_11") (pintype "bidirectional"))
      (node (ref "IC3") (pin "12") (pinfunction "NC_12") (pintype "bidirectional"))
      (node (ref "IC3") (pin "13") (pinfunction "GND_13") (pintype "bidirectional"))
      (node (ref "IC3") (pin "5") (pinfunction "NC_5") (pintype "bidirectional"))
      (node (ref "IC3") (pin "6") (pinfunction "NC_6") (pintype "bidirectional"))
      (node (ref "IC3") (pin "7") (pinfunction "NC_7") (pintype "bidirectional"))
      (node (ref "IC3") (pin "8") (pinfunction "NC_8") (pintype "bidirectional"))
      (node (ref "IC3") (pin "9") (pinfunction "NC_9") (pintype "bidirectional"))
      (node (ref "JP1") (pin "6") (pinfunction "6_6") (pintype "passive"))
      (node (ref "L1") (pin "1") (pinfunction "1_1") (pintype "passive"))
      (node (ref "L2") (pin "1") (pinfunction "1_1") (pintype "passive"))
      (node (ref "L5") (pin "1") (pinfunction "1_1") (pintype "passive"))
      (node (ref "LED1") (pin "C") (pinfunction "C_C") (pintype "passive"))
      (node (ref "LED2") (pin "C") (pinfunction "C_C") (pintype "passive"))
      (node (ref "OOBD2-CONNECTOR") (pin "3") (pinfunction "3_3") (pintype "passive"))
      (node (ref "OOBDPICAN") (pin "5") (pinfunction "5_5") (pintype "passive"))
      (node (ref "PWR_LED") (pin "C") (pinfunction "C_C") (pintype "passive"))
      (node (ref "R12") (pin "2") (pinfunction "2_2") (pintype "passive"))
      (node (ref "R15") (pin "1") (pinfunction "1_1") (pintype "passive"))
      (node (ref "R16") (pin "1") (pinfunction "1_1") (pintype "passive"))
      (node (ref "R17") (pin "1") (pinfunction "1_1") (pintype "passive"))
      (node (ref "R18") (pin "1") (pinfunction "1_1") (pintype "passive"))
      (node (ref "R19") (pin "1") (pinfunction "1_1") (pintype "passive"))
      (node (ref "R31") (pin "2") (pinfunction "2_2") (pintype "passive"))
      (node (ref "R35") (pin "2") (pinfunction "2_2") (pintype "passive"))
      (node (ref "R36") (pin "2") (pinfunction "2_2") (pintype "passive"))
      (node (ref "R5") (pin "2") (pinfunction "2_2") (pintype "passive"))
      (node (ref "TLV320AIC1") (pin "16") (pinfunction "DRVSS_16") (pintype "bidirectional"))
      (node (ref "TLV320AIC1") (pin "24") (pinfunction "SPVSS_24") (pintype "bidirectional"))
      (node (ref "TLV320AIC1") (pin "39") (pinfunction "DVSS_39") (pintype "bidirectional"))
      (node (ref "U1") (pin "2") (pinfunction "VSS_2") (pintype "power_in"))
      (node (ref "U2") (pin "2") (pinfunction "VSS_2") (pintype "power_in"))
      (node (ref "U3") (pin "2") (pinfunction "GND_2") (pintype "power_in"))
      (node (ref "U4") (pin "2") (pinfunction "GND_2") (pintype "power_in"))
      (node (ref "U5") (pin "4") (pinfunction "GND_4") (pintype "bidirectional"))
      (node (ref "U6") (pin "2") (pinfunction "GND_2") (pintype "input"))
      (node (ref "USB_HOST") (pin "4") (pinfunction "4_4") (pintype "passive"))
      (node (ref "USB_OTG") (pin "GND") (pinfunction "GND_GND") (pintype "power_in"))
    )
    (net (code "19") (name "HS-CAN_H") (class "Default")
      (node (ref "D1") (pin "2") (pinfunction "C2_2") (pintype "bidirectional"))
      (node (ref "OOBD2-CONNECTOR") (pin "7") (pinfunction "7_7") (pintype "passive"))
      (node (ref "R2") (pin "2") (pinfunction "2_2") (pintype "passive"))
      (node (ref "U1") (pin "7") (pinfunction "CANH_7") (pintype "output"))
    )
    (net (code "20") (name "HS-CAN_L") (class "Default")
      (node (ref "D1") (pin "1") (pinfunction "C1_1") (pintype "bidirectional"))
      (node (ref "HS-CAN") (pin "1") (pinfunction "1_1") (pintype "passive"))
      (node (ref "OOBD2-CONNECTOR") (pin "6") (pinfunction "6_6") (pintype "passive"))
      (node (ref "U1") (pin "6") (pinfunction "CANL_6") (pintype "output"))
    )
    (net (code "21") (name "HS-CAN_RS") (class "Default")
      (node (ref "AM3352-SOM-EVB-PLATFORM") (pin "4-26") (pinfunction "P3_8/EMU1_4-26") (pintype "passive"))
      (node (ref "R4") (pin "2") (pinfunction "2_2") (pintype "passive"))
    )
    (net (code "22") (name "I2C0-SCL") (class "Default")
      (node (ref "AM3352-SOM-EVB-PLATFORM") (pin "4-15") (pinfunction "P3_6/I2C0-SCL_4-15") (pintype "passive"))
      (node (ref "IC3") (pin "16") (pinfunction "SCL_16") (pintype "bidirectional"))
      (node (ref "R26") (pin "1") (pinfunction "1_1") (pintype "passive"))
      (node (ref "TLV320AIC1") (pin "1") (pinfunction "SCL_1") (pintype "bidirectional"))
    )
    (net (code "23") (name "I2C0-SDA") (class "Default")
      (node (ref "AM3352-SOM-EVB-PLATFORM") (pin "4-16") (pinfunction "P3_5/I2C0-SDA_4-16") (pintype "passive"))
      (node (ref "IC3") (pin "15") (pinfunction "SDA_15") (pintype "bidirectional"))
      (node (ref "R27") (pin "1") (pinfunction "1_1") (pintype "passive"))
      (node (ref "TLV320AIC1") (pin "2") (pinfunction "SDA_2") (pintype "bidirectional"))
    )
    (net (code "24") (name "LED1") (class "Default")
      (node (ref "AM3352-SOM-EVB-PLATFORM") (pin "4-21") (pinfunction "P3_18/LED1_4-21") (pintype "passive"))
      (node (ref "R38") (pin "1") (pinfunction "1_1") (pintype "passive"))
    )
    (net (code "25") (name "LED2") (class "Default")
      (node (ref "AM3352-SOM-EVB-PLATFORM") (pin "4-23") (pinfunction "P3_20/LED2_4-23") (pintype "passive"))
      (node (ref "R40") (pin "1") (pinfunction "1_1") (pintype "passive"))
    )
    (net (code "26") (name "MS-CAN_H") (class "Default")
      (node (ref "D2") (pin "2") (pinfunction "C2_2") (pintype "bidirectional"))
      (node (ref "OOBD2-CONNECTOR") (pin "1") (pinfunction "1_1") (pintype "passive"))
      (node (ref "R9") (pin "2") (pinfunction "2_2") (pintype "passive"))
      (node (ref "U2") (pin "7") (pinfunction "CANH_7") (pintype "output"))
    )
    (net (code "27") (name "MS-CAN_L") (class "Default")
      (node (ref "D2") (pin "1") (pinfunction "C1_1") (pintype "bidirectional"))
      (node (ref "MS-CAN") (pin "1") (pinfunction "1_1") (pintype "passive"))
      (node (ref "OOBD2-CONNECTOR") (pin "2") (pinfunction "2_2") (pintype "passive"))
      (node (ref "U2") (pin "6") (pinfunction "CANL_6") (pintype "output"))
    )
    (net (code "28") (name "MS-CAN_RS") (class "Default")
      (node (ref "AM3352-SOM-EVB-PLATFORM") (pin "4-25") (pinfunction "P3_7/EMU0_4-25") (pintype "passive"))
      (node (ref "R11") (pin "2") (pinfunction "2_2") (pintype "passive"))
    )
    (net (code "29") (name "Net-(BAT1-+)") (class "Default")
      (node (ref "BAT1") (pin "VCC@1") (pinfunction "+_VCC@1") (pintype "power_in"))
      (node (ref "IC3") (pin "14") (pinfunction "VBAT_14") (pintype "bidirectional"))
    )
    (net (code "30") (name "Net-(C3-Pad1)") (class "Default")
      (node (ref "C3") (pin "1") (pinfunction "1_1") (pintype "passive"))
      (node (ref "R2") (pin "1") (pinfunction "1_1") (pintype "passive"))
      (node (ref "R3") (pin "1") (pinfunction "1_1") (pintype "passive"))
    )
    (net (code "31") (name "Net-(C14-Pad1)") (class "Default")
      (node (ref "C14") (pin "1") (pinfunction "1_1") (pintype "passive"))
      (node (ref "R10") (pin "1") (pinfunction "1_1") (pintype "passive"))
      (node (ref "R9") (pin "1") (pinfunction "1_1") (pintype "passive"))
    )
    (net (code "32") (name "Net-(C24-Pad1)") (class "Default")
      (node (ref "C24") (pin "1") (pinfunction "1_1") (pintype "passive"))
      (node (ref "L4") (pin "2") (pinfunction "2_2") (pintype "passive"))
      (node (ref "USB_HOST") (pin "1") (pinfunction "1_1") (pintype "passive"))
    )
    (net (code "33") (name "Net-(C45-Pad2)") (class "Default")
      (node (ref "C45") (pin "2") (pinfunction "2_2") (pintype "passive"))
      (node (ref "JP1") (pin "4") (pinfunction "4_4") (pintype "passive"))
      (node (ref "R29") (pin "2") (pinfunction "2_2") (pintype "passive"))
    )
    (net (code "34") (name "Net-(C46-Pad2)") (class "Default")
      (node (ref "C46") (pin "2") (pinfunction "2_2") (pintype "passive"))
      (node (ref "JP1") (pin "2") (pinfunction "2_2") (pintype "passive"))
      (node (ref "R28") (pin "2") (pinfunction "2_2") (pintype "passive"))
    )
    (net (code "35") (name "Net-(C49-Pad1)") (class "Default")
      (node (ref "C49") (pin "1") (pinfunction "1_1") (pintype "passive"))
      (node (ref "R31") (pin "1") (pinfunction "1_1") (pintype "passive"))
      (node (ref "R34") (pin "2") (pinfunction "2_2") (pintype "passive"))
      (node (ref "WAKE-UP") (pin "2") (pinfunction "2_2") (pintype "passive"))
    )
    (net (code "36") (name "Net-(C52-Pad2)") (class "Default")
      (node (ref "C52") (pin "2") (pinfunction "2_2") (pintype "passive"))
      (node (ref "R35") (pin "1") (pinfunction "1_1") (pintype "passive"))
    )
    (net (code "37") (name "Net-(HS-CAN-Pad2)") (class "Default")
      (node (ref "HS-CAN") (pin "2") (pinfunction "2_2") (pintype "passive"))
      (node (ref "R3") (pin "2") (pinfunction "2_2") (pintype "passive"))
    )
    (net (code "38") (name "Net-(IC3-~{INT})") (class "Default")
      (node (ref "IC3") (pin "3") (pinfunction "~{INT}_3") (pintype "bidirectional"))
      (node (ref "R33") (pin "1") (pinfunction "1_1") (pintype "passive"))
    )
    (net (code "39") (name "Net-(L1-Pad2)") (class "Default")
      (node (ref "L1") (pin "2") (pinfunction "2_2") (pintype "passive"))
      (node (ref "USB_OTG") (pin "GND1") (pinfunction "GND1_GND1") (pintype "input"))
      (node (ref "USB_OTG") (pin "GND2") (pinfunction "GND2_GND2") (pintype "input"))
      (node (ref "USB_OTG") (pin "GND3") (pinfunction "GND3_GND3") (pintype "input"))
      (node (ref "USB_OTG") (pin "GND4") (pinfunction "GND4_GND4") (pintype "input"))
    )
    (net (code "40") (name "Net-(LED1-PadA)") (class "Default")
      (node (ref "LED1") (pin "A") (pinfunction "A_A") (pintype "passive"))
      (node (ref "R38") (pin "2") (pinfunction "2_2") (pintype "passive"))
    )
    (net (code "41") (name "Net-(LED2-PadA)") (class "Default")
      (node (ref "LED2") (pin "A") (pinfunction "A_A") (pintype "passive"))
      (node (ref "R40") (pin "2") (pinfunction "2_2") (pintype "passive"))
    )
    (net (code "42") (name "Net-(MS-CAN-Pad2)") (class "Default")
      (node (ref "MS-CAN") (pin "2") (pinfunction "2_2") (pintype "passive"))
      (node (ref "R10") (pin "2") (pinfunction "2_2") (pintype "passive"))
    )
    (net (code "43") (name "Net-(PWR_LED-PadA)") (class "Default")
      (node (ref "PWR_LED") (pin "A") (pinfunction "A_A") (pintype "passive"))
      (node (ref "R39") (pin "2") (pinfunction "2_2") (pintype "passive"))
    )
    (net (code "44") (name "Net-(R30-Pad1)") (class "Default")
      (node (ref "R30") (pin "1") (pinfunction "1_1") (pintype "passive"))
      (node (ref "WAKE-UP") (pin "1") (pinfunction "1_1") (pintype "passive"))
    )
    (net (code "45") (name "Net-(TLV320AIC1-LEFT_LOP)") (class "Default")
      (node (ref "JP1") (pin "3") (pinfunction "3_3") (pintype "passive"))
      (node (ref "TLV320AIC1") (pin "19") (pinfunction "LEFT_LOP_19") (pintype "bidirectional"))
    )
    (net (code "46") (name "Net-(TLV320AIC1-RIGHT_LOP)") (class "Default")
      (node (ref "JP1") (pin "1") (pinfunction "1_1") (pintype "passive"))
      (node (ref "TLV320AIC1") (pin "20") (pinfunction "RIGHT_LOP_20") (pintype "bidirectional"))
    )
    (net (code "47") (name "Net-(TLV320AIC1-SPOM)") (class "Default")
      (node (ref "R29") (pin "1") (pinfunction "1_1") (pintype "passive"))
      (node (ref "TLV320AIC1") (pin "23") (pinfunction "SPOM_23") (pintype "bidirectional"))
    )
    (net (code "48") (name "Net-(TLV320AIC1-SPOP)") (class "Default")
      (node (ref "R28") (pin "1") (pinfunction "1_1") (pintype "passive"))
      (node (ref "TLV320AIC1") (pin "26") (pinfunction "SPOP_26") (pintype "bidirectional"))
    )
    (net (code "49") (name "Net-(U1-RS)") (class "Default")
      (node (ref "R4") (pin "1") (pinfunction "1_1") (pintype "passive"))
      (node (ref "R5") (pin "1") (pinfunction "1_1") (pintype "passive"))
      (node (ref "U1") (pin "8") (pinfunction "RS_8") (pintype "input"))
    )
    (net (code "50") (name "Net-(U2-RS)") (class "Default")
      (node (ref "R11") (pin "1") (pinfunction "1_1") (pintype "passive"))
      (node (ref "R12") (pin "1") (pinfunction "1_1") (pintype "passive"))
      (node (ref "U2") (pin "8") (pinfunction "RS_8") (pintype "input"))
    )
    (net (code "51") (name "Net-(U3-EN)") (class "Default")
      (node (ref "R17") (pin "2") (pinfunction "2_2") (pintype "passive"))
      (node (ref "R21") (pin "1") (pinfunction "1_1") (pintype "passive"))
      (node (ref "R22") (pin "1") (pinfunction "1_1") (pintype "passive"))
      (node (ref "U3") (pin "4") (pinfunction "EN_4") (pintype "bidirectional"))
    )
    (net (code "52") (name "Net-(U3-ISET)") (class "Default")
      (node (ref "R15") (pin "2") (pinfunction "2_2") (pintype "passive"))
      (node (ref "U3") (pin "3") (pinfunction "ISET_3") (pintype "bidirectional"))
    )
    (net (code "53") (name "Net-(U3-OUT)") (class "Default")
      (node (ref "C25") (pin "1") (pinfunction "1_1") (pintype "passive"))
      (node (ref "C27") (pin "1") (pinfunction "1_1") (pintype "passive"))
      (node (ref "L3") (pin "2") (pinfunction "2_2") (pintype "passive"))
      (node (ref "R20") (pin "2") (pinfunction "2_2") (pintype "passive"))
      (node (ref "U3") (pin "1") (pinfunction "OUT_1") (pintype "bidirectional"))
    )
    (net (code "54") (name "Net-(U4-EN)") (class "Default")
      (node (ref "R18") (pin "2") (pinfunction "2_2") (pintype "passive"))
      (node (ref "R24") (pin "1") (pinfunction "1_1") (pintype "passive"))
      (node (ref "R25") (pin "1") (pinfunction "1_1") (pintype "passive"))
      (node (ref "U4") (pin "4") (pinfunction "EN_4") (pintype "bidirectional"))
    )
    (net (code "55") (name "Net-(U4-ISET)") (class "Default")
      (node (ref "R16") (pin "2") (pinfunction "2_2") (pintype "passive"))
      (node (ref "U4") (pin "3") (pinfunction "ISET_3") (pintype "bidirectional"))
    )
    (net (code "56") (name "Net-(U4-OUT)") (class "Default")
      (node (ref "C26") (pin "1") (pinfunction "1_1") (pintype "passive"))
      (node (ref "C28") (pin "1") (pinfunction "1_1") (pintype "passive"))
      (node (ref "L4") (pin "1") (pinfunction "1_1") (pintype "passive"))
      (node (ref "R23") (pin "2") (pinfunction "2_2") (pintype "passive"))
      (node (ref "U4") (pin "1") (pinfunction "OUT_1") (pintype "bidirectional"))
    )
    (net (code "57") (name "Net-(U5-BS)") (class "Default")
      (node (ref "C51") (pin "1") (pinfunction "1_1") (pintype "passive"))
      (node (ref "U5") (pin "1") (pinfunction "BS_1") (pintype "bidirectional"))
    )
    (net (code "58") (name "Net-(U5-COMP)") (class "Default")
      (node (ref "C52") (pin "1") (pinfunction "1_1") (pintype "passive"))
      (node (ref "U5") (pin "6") (pinfunction "COMP_6") (pintype "bidirectional"))
    )
    (net (code "59") (name "Net-(U5-EN)") (class "Default")
      (node (ref "R32") (pin "2") (pinfunction "2_2") (pintype "passive"))
      (node (ref "U5") (pin "7") (pinfunction "EN_7") (pintype "bidirectional"))
    )
    (net (code "60") (name "Net-(U5-FB)") (class "Default")
      (node (ref "R36") (pin "1") (pinfunction "1_1") (pintype "passive"))
      (node (ref "R37") (pin "1") (pinfunction "1_1") (pintype "passive"))
      (node (ref "U5") (pin "5") (pinfunction "FB_5") (pintype "bidirectional"))
    )
    (net (code "61") (name "Net-(U5-SS)") (class "Default")
      (node (ref "C50") (pin "1") (pinfunction "1_1") (pintype "passive"))
      (node (ref "U5") (pin "8") (pinfunction "SS_8") (pintype "bidirectional"))
    )
    (net (code "62") (name "Net-(U5-SW)") (class "Default")
      (node (ref "C51") (pin "2") (pinfunction "2_2") (pintype "passive"))
      (node (ref "L6") (pin "1") (pinfunction "1_1") (pintype "passive"))
      (node (ref "U5") (pin "3") (pinfunction "SW_3") (pintype "bidirectional"))
    )
    (net (code "63") (name "Net-(U6-BP)") (class "Default")
      (node (ref "C58") (pin "2") (pinfunction "2_2") (pintype "passive"))
      (node (ref "U6") (pin "4") (pinfunction "BP_4") (pintype "input"))
    )
    (net (code "64") (name "Net-(USB_HOST-5)") (class "Default")
      (node (ref "L2") (pin "2") (pinfunction "2_2") (pintype "passive"))
      (node (ref "USB_HOST") (pin "P$1") (pinfunction "5_P$1") (pintype "input"))
      (node (ref "USB_HOST") (pin "P$2") (pinfunction "6_P$2") (pintype "input"))
    )
    (net (code "65") (name "SYS_RESETN") (class "Default")
      (node (ref "AM3352-SOM-EVB-PLATFORM") (pin "4-28") (pinfunction "SYS_RESETN_4-28") (pintype "passive"))
      (node (ref "IC3") (pin "4") (pinfunction "~{RST}_4") (pintype "bidirectional"))
      (node (ref "TLV320AIC1") (pin "31") (pinfunction "RESETN_31") (pintype "bidirectional"))
    )
    (net (code "66") (name "USB0_CE") (class "Default")
      (node (ref "AM3352-SOM-EVB-PLATFORM") (pin "3-14") (pinfunction "USB0_CE_3-14") (pintype "passive"))
      (node (ref "R21") (pin "2") (pinfunction "2_2") (pintype "passive"))
    )
    (net (code "67") (name "USB0_DM") (class "Default")
      (node (ref "AM3352-SOM-EVB-PLATFORM") (pin "3-15") (pinfunction "USB0_DM_3-15") (pintype "passive"))
      (node (ref "USB_OTG") (pin "D-") (pinfunction "D-_D-") (pintype "input"))
    )
    (net (code "68") (name "USB0_DP") (class "Default")
      (node (ref "AM3352-SOM-EVB-PLATFORM") (pin "3-13") (pinfunction "USB0_DP_3-13") (pintype "passive"))
      (node (ref "USB_OTG") (pin "D+") (pinfunction "D+_D+") (pintype "input"))
    )
    (net (code "69") (name "USB0_DRV") (class "Default")
      (node (ref "AM3352-SOM-EVB-PLATFORM") (pin "3-16") (pinfunction "USB0-DRV_3-16") (pintype "passive"))
      (node (ref "R22") (pin "2") (pinfunction "2_2") (pintype "passive"))
    )
    (net (code "70") (name "USB0_ID") (class "Default")
      (node (ref "AM3352-SOM-EVB-PLATFORM") (pin "3-12") (pinfunction "USB0-ID_3-12") (pintype "passive"))
      (node (ref "USB_OTG") (pin "ID") (pinfunction "ID_ID") (pintype "input"))
    )
    (net (code "71") (name "USB0_VBUS") (class "Default")
      (node (ref "AM3352-SOM-EVB-PLATFORM") (pin "3-11") (pinfunction "USB0-VBUS_3-11") (pintype "passive"))
      (node (ref "R20") (pin "1") (pinfunction "1_1") (pintype "passive"))
    )
    (net (code "72") (name "USB1_CE") (class "Default")
      (node (ref "AM3352-SOM-EVB-PLATFORM") (pin "3-8") (pinfunction "USB1_CE_3-8") (pintype "passive"))
      (node (ref "R24") (pin "2") (pinfunction "2_2") (pintype "passive"))
    )
    (net (code "73") (name "USB1_DM") (class "Default")
      (node (ref "AM3352-SOM-EVB-PLATFORM") (pin "3-9") (pinfunction "USB1_DM_3-9") (pintype "passive"))
      (node (ref "OOBDPICAN") (pin "2") (pinfunction "2_2") (pintype "passive"))
      (node (ref "USB_HOST") (pin "2") (pinfunction "2_2") (pintype "passive"))
    )
    (net (code "74") (name "USB1_DP") (class "Default")
      (node (ref "AM3352-SOM-EVB-PLATFORM") (pin "3-7") (pinfunction "USB1_DP_3-7") (pintype "passive"))
      (node (ref "OOBDPICAN") (pin "4") (pinfunction "4_4") (pintype "passive"))
      (node (ref "USB_HOST") (pin "3") (pinfunction "3_3") (pintype "passive"))
    )
    (net (code "75") (name "USB1_DRV") (class "Default")
      (node (ref "AM3352-SOM-EVB-PLATFORM") (pin "3-10") (pinfunction "USB1_DRV_3-10") (pintype "passive"))
      (node (ref "R25") (pin "2") (pinfunction "2_2") (pintype "passive"))
    )
    (net (code "76") (name "USB1_ID") (class "Default")
      (node (ref "AM3352-SOM-EVB-PLATFORM") (pin "3-6") (pinfunction "USB1_ID_3-6") (pintype "passive"))
      (node (ref "R19") (pin "2") (pinfunction "2_2") (pintype "passive"))
    )
    (net (code "77") (name "USB1_VBUS") (class "Default")
      (node (ref "AM3352-SOM-EVB-PLATFORM") (pin "3-5") (pinfunction "USB1-VBUS_3-5") (pintype "passive"))
      (node (ref "R23") (pin "1") (pinfunction "1_1") (pintype "passive"))
    )
    (net (code "78") (name "unconnected-(AM3352-SOM-EVB-PLATFORM-AIN4-Pad4-35)") (class "Default")
      (node (ref "AM3352-SOM-EVB-PLATFORM") (pin "4-35") (pinfunction "AIN4_4-35") (pintype "passive"))
    )
    (net (code "79") (name "unconnected-(AM3352-SOM-EVB-PLATFORM-AIN5-Pad4-37)") (class "Default")
      (node (ref "AM3352-SOM-EVB-PLATFORM") (pin "4-37") (pinfunction "AIN5_4-37") (pintype "passive"))
    )
    (net (code "80") (name "unconnected-(AM3352-SOM-EVB-PLATFORM-AIN6-Pad4-38)") (class "Default")
      (node (ref "AM3352-SOM-EVB-PLATFORM") (pin "4-38") (pinfunction "AIN6_4-38") (pintype "passive"))
    )
    (net (code "81") (name "unconnected-(AM3352-SOM-EVB-PLATFORM-AIN7-Pad4-36)") (class "Default")
      (node (ref "AM3352-SOM-EVB-PLATFORM") (pin "4-36") (pinfunction "AIN7_4-36") (pintype "passive"))
    )
    (net (code "82") (name "unconnected-(AM3352-SOM-EVB-PLATFORM-JTAG_TCK-Pad4-29)") (class "Default")
      (node (ref "AM3352-SOM-EVB-PLATFORM") (pin "4-29") (pinfunction "JTAG_TCK_4-29") (pintype "passive"))
    )
    (net (code "83") (name "unconnected-(AM3352-SOM-EVB-PLATFORM-JTAG_TDI-Pad4-31)") (class "Default")
      (node (ref "AM3352-SOM-EVB-PLATFORM") (pin "4-31") (pinfunction "JTAG_TDI_4-31") (pintype "passive"))
    )
    (net (code "84") (name "unconnected-(AM3352-SOM-EVB-PLATFORM-JTAG_TDO-Pad4-33)") (class "Default")
      (node (ref "AM3352-SOM-EVB-PLATFORM") (pin "4-33") (pinfunction "JTAG_TDO_4-33") (pintype "passive"))
    )
    (net (code "85") (name "unconnected-(AM3352-SOM-EVB-PLATFORM-JTAG_TMS-Pad4-32)") (class "Default")
      (node (ref "AM3352-SOM-EVB-PLATFORM") (pin "4-32") (pinfunction "JTAG_TMS_4-32") (pintype "passive"))
    )
    (net (code "86") (name "unconnected-(AM3352-SOM-EVB-PLATFORM-JTAG_TRST-Pad4-30)") (class "Default")
      (node (ref "AM3352-SOM-EVB-PLATFORM") (pin "4-30") (pinfunction "JTAG_TRST_4-30") (pintype "passive"))
    )
    (net (code "87") (name "unconnected-(AM3352-SOM-EVB-PLATFORM-MMC0-SDCD#{slash}EMU4-Pad3-17)") (class "Default")
      (node (ref "AM3352-SOM-EVB-PLATFORM") (pin "3-17") (pinfunction "MMC0-SDCD#/EMU4_3-17") (pintype "passive"))
    )
    (net (code "88") (name "unconnected-(AM3352-SOM-EVB-PLATFORM-NNMI-Pad3-22)") (class "Default")
      (node (ref "AM3352-SOM-EVB-PLATFORM") (pin "3-22") (pinfunction "NNMI_3-22") (pintype "passive"))
    )
    (net (code "89") (name "unconnected-(AM3352-SOM-EVB-PLATFORM-P0_0{slash}EMDIO-Pad3-38)") (class "Default")
      (node (ref "AM3352-SOM-EVB-PLATFORM") (pin "3-38") (pinfunction "P0_0/EMDIO_3-38") (pintype "passive"))
    )
    (net (code "90") (name "unconnected-(AM3352-SOM-EVB-PLATFORM-P0_1{slash}EMDC-Pad3-36)") (class "Default")
      (node (ref "AM3352-SOM-EVB-PLATFORM") (pin "3-36") (pinfunction "P0_1/EMDC_3-36") (pintype "passive"))
    )
    (net (code "91") (name "unconnected-(AM3352-SOM-EVB-PLATFORM-P0_2{slash}SPI0_SCLK-Pad4-11)") (class "Default")
      (node (ref "AM3352-SOM-EVB-PLATFORM") (pin "4-11") (pinfunction "P0_2/SPI0_SCLK_4-11") (pintype "passive"))
    )
    (net (code "92") (name "unconnected-(AM3352-SOM-EVB-PLATFORM-P0_3{slash}SPI0_D0(MISO)-Pad4-9)") (class "Default")
      (node (ref "AM3352-SOM-EVB-PLATFORM") (pin "4-9") (pinfunction "P0_3/SPI0_D0(MISO)_4-9") (pintype "passive"))
    )
    (net (code "93") (name "unconnected-(AM3352-SOM-EVB-PLATFORM-P0_4{slash}SPI0_D1(MOSI)-Pad4-10)") (class "Default")
      (node (ref "AM3352-SOM-EVB-PLATFORM") (pin "4-10") (pinfunction "P0_4/SPI0_D1(MOSI)_4-10") (pintype "passive"))
    )
    (net (code "94") (name "unconnected-(AM3352-SOM-EVB-PLATFORM-P0_5{slash}SPI0_CS0-Pad4-12)") (class "Default")
      (node (ref "AM3352-SOM-EVB-PLATFORM") (pin "4-12") (pinfunction "P0_5/SPI0_CS0_4-12") (pintype "passive"))
    )
    (net (code "95") (name "unconnected-(AM3352-SOM-EVB-PLATFORM-P0_7{slash}PWM0_OUT-Pad4-27)") (class "Default")
      (node (ref "AM3352-SOM-EVB-PLATFORM") (pin "4-27") (pinfunction "P0_7/PWM0_OUT_4-27") (pintype "passive"))
    )
    (net (code "96") (name "unconnected-(AM3352-SOM-EVB-PLATFORM-P0_14{slash}UART1_RXD-Pad4-6)") (class "Default")
      (node (ref "AM3352-SOM-EVB-PLATFORM") (pin "4-6") (pinfunction "P0_14/UART1_RXD_4-6") (pintype "passive"))
    )
    (net (code "97") (name "unconnected-(AM3352-SOM-EVB-PLATFORM-P0_15{slash}UART1_TXD-Pad4-5)") (class "Default")
      (node (ref "AM3352-SOM-EVB-PLATFORM") (pin "4-5") (pinfunction "P0_15/UART1_TXD_4-5") (pintype "passive"))
    )
    (net (code "98") (name "unconnected-(AM3352-SOM-EVB-PLATFORM-P0_16{slash}ETXD3-Pad3-29)") (class "Default")
      (node (ref "AM3352-SOM-EVB-PLATFORM") (pin "3-29") (pinfunction "P0_16/ETXD3_3-29") (pintype "passive"))
    )
    (net (code "99") (name "unconnected-(AM3352-SOM-EVB-PLATFORM-P0_17{slash}ETXD2-Pad3-27)") (class "Default")
      (node (ref "AM3352-SOM-EVB-PLATFORM") (pin "3-27") (pinfunction "P0_17/ETXD2_3-27") (pintype "passive"))
    )
    (net (code "100") (name "unconnected-(AM3352-SOM-EVB-PLATFORM-P0_20{slash}EMU3-Pad4-22)") (class "Default")
      (node (ref "AM3352-SOM-EVB-PLATFORM") (pin "4-22") (pinfunction "P0_20/EMU3_4-22") (pintype "passive"))
    )
    (net (code "101") (name "unconnected-(AM3352-SOM-EVB-PLATFORM-P0_21{slash}ETXD1-Pad3-25)") (class "Default")
      (node (ref "AM3352-SOM-EVB-PLATFORM") (pin "3-25") (pinfunction "P0_21/ETXD1_3-25") (pintype "passive"))
    )
    (net (code "102") (name "unconnected-(AM3352-SOM-EVB-PLATFORM-P0_28{slash}ETXD0-Pad3-23)") (class "Default")
      (node (ref "AM3352-SOM-EVB-PLATFORM") (pin "3-23") (pinfunction "P0_28/ETXD0_3-23") (pintype "passive"))
    )
    (net (code "103") (name "unconnected-(AM3352-SOM-EVB-PLATFORM-P0_29{slash}EPHY-RST#{slash}RFCLK-Pad3-40)") (class "Default")
      (node (ref "AM3352-SOM-EVB-PLATFORM") (pin "3-40") (pinfunction "P0_29/EPHY-RST#/RFCLK_3-40") (pintype "passive"))
    )
    (net (code "104") (name "unconnected-(AM3352-SOM-EVB-PLATFORM-P2_18{slash}ERXD3-Pad3-30)") (class "Default")
      (node (ref "AM3352-SOM-EVB-PLATFORM") (pin "3-30") (pinfunction "P2_18/ERXD3_3-30") (pintype "passive"))
    )
    (net (code "105") (name "unconnected-(AM3352-SOM-EVB-PLATFORM-P2_19{slash}ERXD2-Pad3-28)") (class "Default")
      (node (ref "AM3352-SOM-EVB-PLATFORM") (pin "3-28") (pinfunction "P2_19/ERXD2_3-28") (pintype "passive"))
    )
    (net (code "106") (name "unconnected-(AM3352-SOM-EVB-PLATFORM-P2_20{slash}ERXD1-Pad3-26)") (class "Default")
      (node (ref "AM3352-SOM-EVB-PLATFORM") (pin "3-26") (pinfunction "P2_20/ERXD1_3-26") (pintype "passive"))
    )
    (net (code "107") (name "unconnected-(AM3352-SOM-EVB-PLATFORM-P2_21{slash}ERXD0-Pad3-24)") (class "Default")
      (node (ref "AM3352-SOM-EVB-PLATFORM") (pin "3-24") (pinfunction "P2_21/ERXD0_3-24") (pintype "passive"))
    )
    (net (code "108") (name "unconnected-(AM3352-SOM-EVB-PLATFORM-P3_0{slash}ECOL-Pad3-37)") (class "Default")
      (node (ref "AM3352-SOM-EVB-PLATFORM") (pin "3-37") (pinfunction "P3_0/ECOL_3-37") (pintype "passive"))
    )
    (net (code "109") (name "unconnected-(AM3352-SOM-EVB-PLATFORM-P3_1{slash}ECRS-Pad3-39)") (class "Default")
      (node (ref "AM3352-SOM-EVB-PLATFORM") (pin "3-39") (pinfunction "P3_1/ECRS_3-39") (pintype "passive"))
    )
    (net (code "110") (name "unconnected-(AM3352-SOM-EVB-PLATFORM-P3_2{slash}ERXERR-Pad3-35)") (class "Default")
      (node (ref "AM3352-SOM-EVB-PLATFORM") (pin "3-35") (pinfunction "P3_2/ERXERR_3-35") (pintype "passive"))
    )
    (net (code "111") (name "unconnected-(AM3352-SOM-EVB-PLATFORM-P3_3{slash}ETXEN-Pad3-31)") (class "Default")
      (node (ref "AM3352-SOM-EVB-PLATFORM") (pin "3-31") (pinfunction "P3_3/ETXEN_3-31") (pintype "passive"))
    )
    (net (code "112") (name "unconnected-(AM3352-SOM-EVB-PLATFORM-P3_4{slash}ERXDV-Pad3-32)") (class "Default")
      (node (ref "AM3352-SOM-EVB-PLATFORM") (pin "3-32") (pinfunction "P3_4/ERXDV_3-32") (pintype "passive"))
    )
    (net (code "113") (name "unconnected-(AM3352-SOM-EVB-PLATFORM-P3_9{slash}ETXCK-Pad3-33)") (class "Default")
      (node (ref "AM3352-SOM-EVB-PLATFORM") (pin "3-33") (pinfunction "P3_9/ETXCK_3-33") (pintype "passive"))
    )
    (net (code "114") (name "unconnected-(AM3352-SOM-EVB-PLATFORM-P3_10{slash}ERXCK-Pad3-34)") (class "Default")
      (node (ref "AM3352-SOM-EVB-PLATFORM") (pin "3-34") (pinfunction "P3_10/ERXCK_3-34") (pintype "passive"))
    )
    (net (code "115") (name "unconnected-(AM3352-SOM-EVB-PLATFORM-PMIC_POWER_EN-Pad3-18)") (class "Default")
      (node (ref "AM3352-SOM-EVB-PLATFORM") (pin "3-18") (pinfunction "PMIC_POWER_EN_3-18") (pintype "passive"))
    )
    (net (code "116") (name "unconnected-(AM3352-SOM-EVB-PLATFORM-PWRONRSTN-Pad3-19)") (class "Default")
      (node (ref "AM3352-SOM-EVB-PLATFORM") (pin "3-19") (pinfunction "PWRONRSTN_3-19") (pintype "passive"))
    )
    (net (code "117") (name "unconnected-(AM3352-SOM-EVB-PLATFORM-SYS_RESETN-Pad3-21)") (class "Default")
      (node (ref "AM3352-SOM-EVB-PLATFORM") (pin "3-21") (pinfunction "SYS_RESETN_3-21") (pintype "passive"))
    )
    (net (code "118") (name "unconnected-(AM3352-SOM-EVB-PLATFORM-VDDA_ADC-Pad4-39)") (class "Default")
      (node (ref "AM3352-SOM-EVB-PLATFORM") (pin "4-39") (pinfunction "VDDA_ADC_4-39") (pintype "passive"))
    )
    (net (code "119") (name "unconnected-(AM3352-SOM-EVB-PLATFORM-VREFP-Pad4-34)") (class "Default")
      (node (ref "AM3352-SOM-EVB-PLATFORM") (pin "4-34") (pinfunction "VREFP_4-34") (pintype "passive"))
    )
    (net (code "120") (name "unconnected-(IC3-32KHZ-Pad1)") (class "Default")
      (node (ref "IC3") (pin "1") (pinfunction "32KHZ_1") (pintype "bidirectional"))
    )
    (net (code "121") (name "unconnected-(OOBD2-CONNECTOR-Pad4)") (class "Default")
      (node (ref "OOBD2-CONNECTOR") (pin "4") (pinfunction "4_4") (pintype "passive"))
    )
    (net (code "122") (name "unconnected-(OOBD2-CONNECTOR-Pad5)") (class "Default")
      (node (ref "OOBD2-CONNECTOR") (pin "5") (pinfunction "5_5") (pintype "passive"))
    )
    (net (code "123") (name "unconnected-(OOBD2-CONNECTOR-Pad8)") (class "Default")
      (node (ref "OOBD2-CONNECTOR") (pin "8") (pinfunction "8_8") (pintype "passive"))
    )
    (net (code "124") (name "unconnected-(OOBD2-CONNECTOR-Pad9)") (class "Default")
      (node (ref "OOBD2-CONNECTOR") (pin "9") (pinfunction "9_9") (pintype "passive"))
    )
    (net (code "125") (name "unconnected-(OOBDPICAN-Pad3)") (class "Default")
      (node (ref "OOBDPICAN") (pin "3") (pinfunction "3_3") (pintype "passive"))
    )
    (net (code "126") (name "unconnected-(OOBDPICAN-Pad6)") (class "Default")
      (node (ref "OOBDPICAN") (pin "6") (pinfunction "6_6") (pintype "passive"))
    )
    (net (code "127") (name "unconnected-(TLV320AIC1-GPIO1-Pad32)") (class "Default")
      (node (ref "TLV320AIC1") (pin "32") (pinfunction "GPIO1_32") (pintype "bidirectional"))
    )
    (net (code "128") (name "unconnected-(TLV320AIC1-HPCOM-Pad15)") (class "Default")
      (node (ref "TLV320AIC1") (pin "15") (pinfunction "HPCOM_15") (pintype "bidirectional"))
    )
    (net (code "129") (name "unconnected-(TLV320AIC1-HPLOUT-Pad14)") (class "Default")
      (node (ref "TLV320AIC1") (pin "14") (pinfunction "HPLOUT_14") (pintype "bidirectional"))
    )
    (net (code "130") (name "unconnected-(TLV320AIC1-HPROUT-Pad17)") (class "Default")
      (node (ref "TLV320AIC1") (pin "17") (pinfunction "HPROUT_17") (pintype "bidirectional"))
    )
    (net (code "131") (name "unconnected-(TLV320AIC1-LINE1LP-Pad4)") (class "Default")
      (node (ref "TLV320AIC1") (pin "4") (pinfunction "LINE1LP_4") (pintype "bidirectional"))
    )
    (net (code "132") (name "unconnected-(TLV320AIC1-LINE1RP-Pad5)") (class "Default")
      (node (ref "TLV320AIC1") (pin "5") (pinfunction "LINE1RP_5") (pintype "bidirectional"))
    )
    (net (code "133") (name "unconnected-(TLV320AIC1-LINE2LP-Pad7)") (class "Default")
      (node (ref "TLV320AIC1") (pin "7") (pinfunction "LINE2LP_7") (pintype "bidirectional"))
    )
    (net (code "134") (name "unconnected-(TLV320AIC1-LINE2RP{slash}LINE2LM-Pad8)") (class "Default")
      (node (ref "TLV320AIC1") (pin "8") (pinfunction "LINE2RP/LINE2LM_8") (pintype "bidirectional"))
    )
    (net (code "135") (name "unconnected-(TLV320AIC1-MIC3L{slash}LINE1RM-Pad6)") (class "Default")
      (node (ref "TLV320AIC1") (pin "6") (pinfunction "MIC3L/LINE1RM_6") (pintype "bidirectional"))
    )
    (net (code "136") (name "unconnected-(TLV320AIC1-MIC3R{slash}LINE2RM-Pad9)") (class "Default")
      (node (ref "TLV320AIC1") (pin "9") (pinfunction "MIC3R/LINE2RM_9") (pintype "bidirectional"))
    )
    (net (code "137") (name "unconnected-(TLV320AIC1-MICBIAS-Pad10)") (class "Default")
      (node (ref "TLV320AIC1") (pin "10") (pinfunction "MICBIAS_10") (pintype "bidirectional"))
    )
    (net (code "138") (name "unconnected-(TLV320AIC1-MICDET{slash}LINE1LM-Pad3)") (class "Default")
      (node (ref "TLV320AIC1") (pin "3") (pinfunction "MICDET/LINE1LM_3") (pintype "bidirectional"))
    )
    (net (code "139") (name "unconnected-(TLV320AIC1-SWOUTM-Pad28)") (class "Default")
      (node (ref "TLV320AIC1") (pin "28") (pinfunction "SWOUTM_28") (pintype "bidirectional"))
    )
    (net (code "140") (name "unconnected-(TLV320AIC1-SWOUTP-Pad29)") (class "Default")
      (node (ref "TLV320AIC1") (pin "29") (pinfunction "SWOUTP_29") (pintype "bidirectional"))
    )
    (net (code "141") (name "unconnected-(U1-VREF-Pad5)") (class "Default")
      (node (ref "U1") (pin "5") (pinfunction "VREF_5") (pintype "output"))
    )
    (net (code "142") (name "unconnected-(U2-VREF-Pad5)") (class "Default")
      (node (ref "U2") (pin "5") (pinfunction "VREF_5") (pintype "output"))
    )
  )
)
